# SAFMR_main.net
KiCad netlist of a schematic drawn in Altium Designer
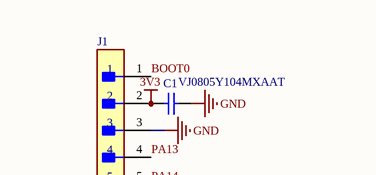
[diagram p0: SAFMR_main.SchDoc, top left]
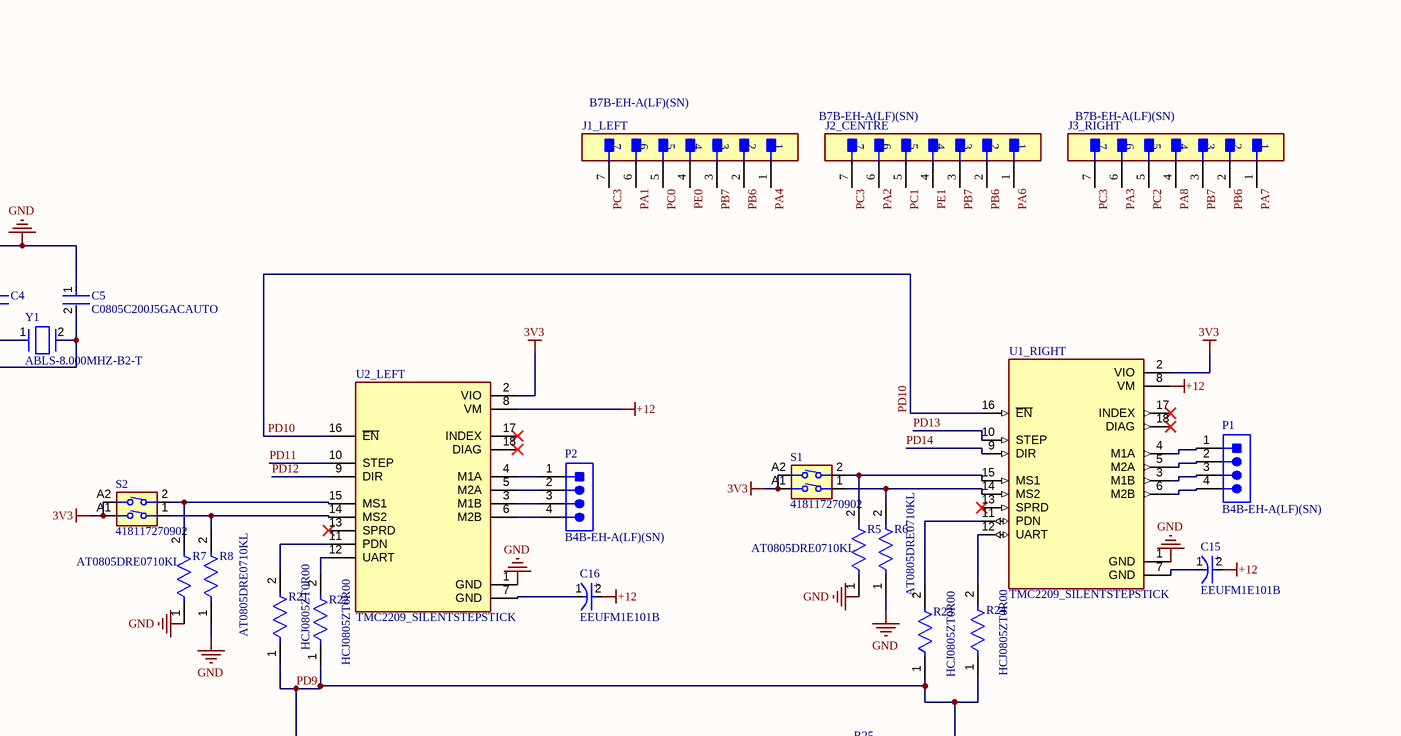
[diagram p1: SAFMR_main.SchDoc, top right]
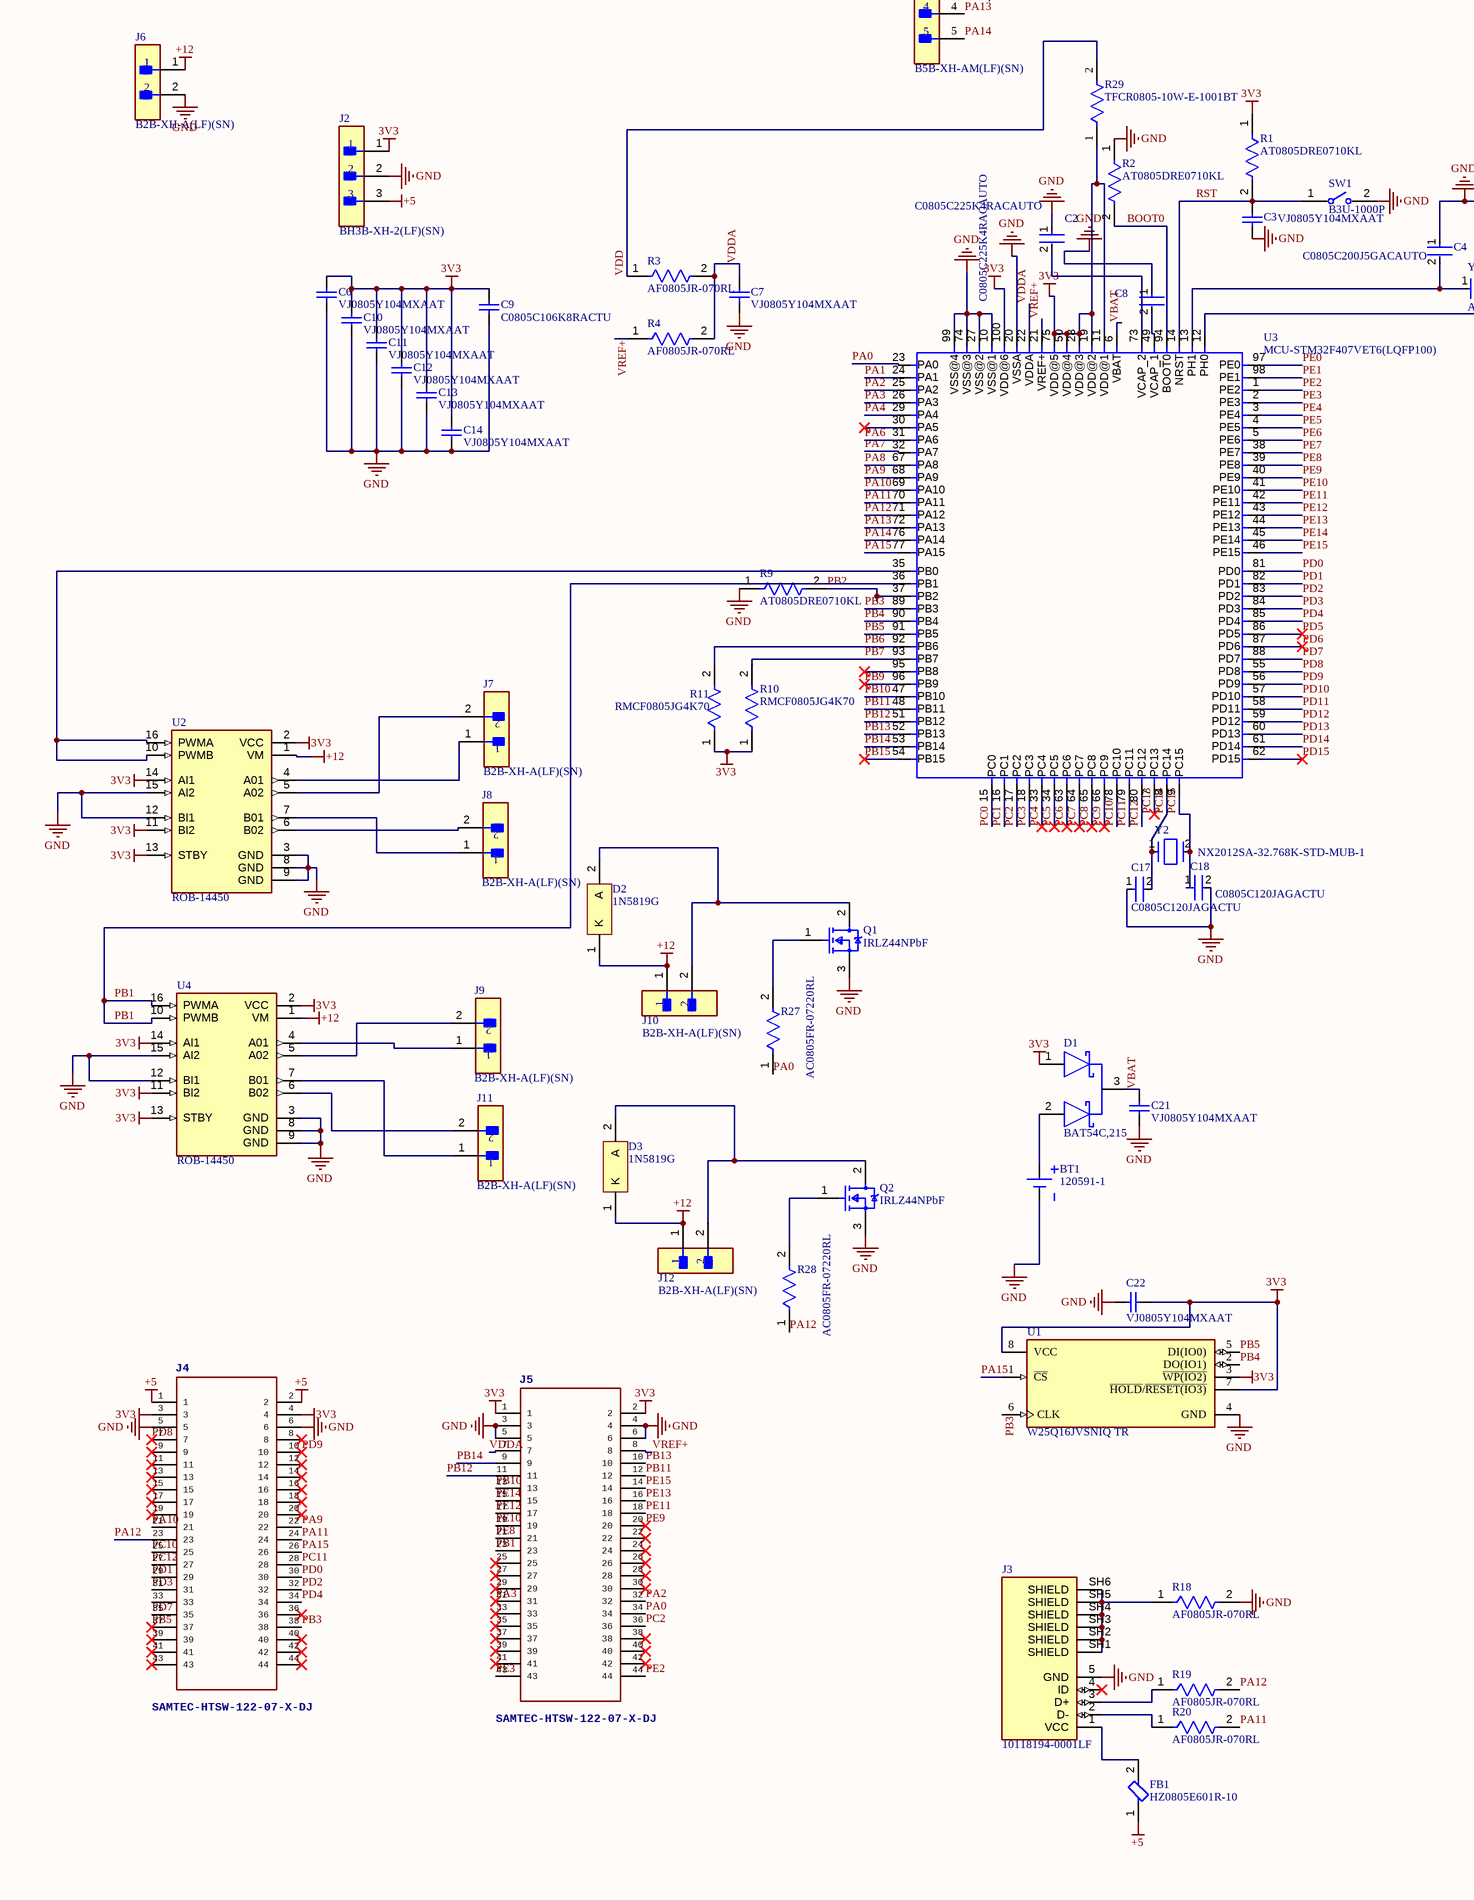
[diagram p2: SAFMR_main.SchDoc, bottom left]
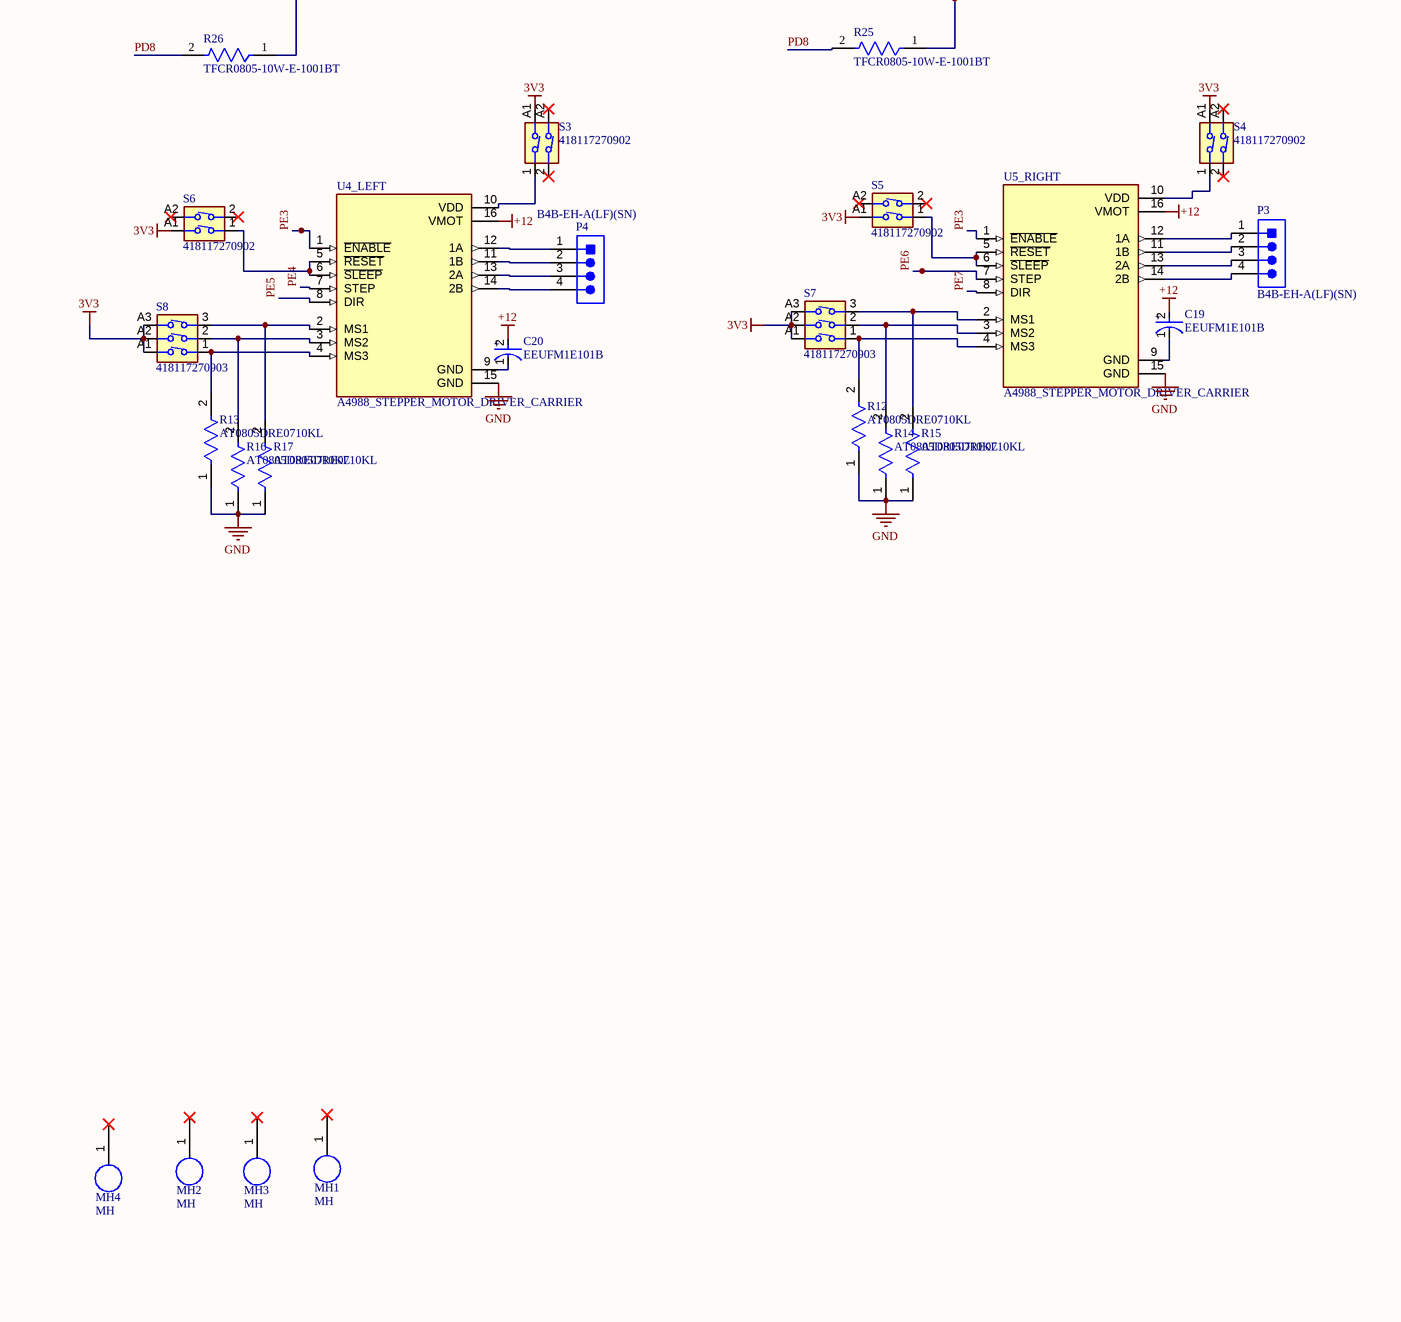
[diagram p3: SAFMR_main.SchDoc, bottom right]

(export (version "E")
  (design (tool "Eeschema 10.0.6"))
  (components
    (comp (ref "BT1")
      (value "120591-1")
      (footprint "TECO-120591-1-2_V")
      (description "Lithium Battery Holder for CR2032 3V Cell")
      (fields (field (name "MANUFACTURER") "TE Connectivity"))
      (libsource (lib "Altium Content Vault") (part "TECO-120591-1-2"))
    )
    (comp (ref "C1")
      (value "VJ0805Y104MXAAT")
      (footprint "CAPC2013X145X48NL20T23")
      (fields (field (name "MANUFACTURER") "Vitramon"))
      (libsource (lib "Altium Content Vault") (part "CAP"))
    )
    (comp (ref "C2")
      (value "C0805C225K4RACAUTO")
      (footprint "FP-C0805C225K4RACAUTO-MFG")
      (description "CAP CER 2.2UF 16V X7R 0805")
      (fields (field (name "TOLERANCE") "10%"))
      (libsource (lib "Altium Content Vault") (part "b4654b650e69147ec39a6b967a45e02"))
    )
    (comp (ref "C3")
      (value "VJ0805Y104MXAAT")
      (footprint "CAPC2013X145X48NL20T23")
      (fields (field (name "MANUFACTURER") "Vitramon"))
      (libsource (lib "Altium Content Vault") (part "CAP"))
    )
    (comp (ref "C4")
      (value "C0805C200J5GACAUTO")
      (footprint "FP-C0805C-DN-MFG")
      (description "C0805 20 pF C0G 30ppm/°C 5.00% 50 V")
      (fields (field (name "MANUFACTURER") "KEMET") (field (name "TOLERANCE") "0.05"))
      (libsource (lib "Altium Content Vault") (part "b4654b650e69147ec39a6b967a45e02"))
    )
    (comp (ref "C5")
      (value "C0805C200J5GACAUTO")
      (footprint "FP-C0805C-DN-MFG")
      (description "C0805 20 pF C0G 30ppm/°C 5.00% 50 V")
      (fields (field (name "MANUFACTURER") "KEMET") (field (name "TOLERANCE") "0.05"))
      (libsource (lib "Altium Content Vault") (part "b4654b650e69147ec39a6b967a45e02"))
    )
    (comp (ref "C6")
      (value "VJ0805Y104MXAAT")
      (footprint "CAPC2013X145X48NL20T23")
      (fields (field (name "MANUFACTURER") "Vitramon"))
      (libsource (lib "Altium Content Vault") (part "CAP"))
    )
    (comp (ref "C7")
      (value "VJ0805Y104MXAAT")
      (footprint "CAPC2013X145X48NL20T23")
      (fields (field (name "MANUFACTURER") "Vitramon"))
      (libsource (lib "Altium Content Vault") (part "CAP"))
    )
    (comp (ref "C8")
      (value "C0805C225K4RACAUTO")
      (footprint "FP-C0805C225K4RACAUTO-MFG")
      (description "CAP CER 2.2UF 16V X7R 0805")
      (fields (field (name "TOLERANCE") "10%"))
      (libsource (lib "Altium Content Vault") (part "b4654b650e69147ec39a6b967a45e02"))
    )
    (comp (ref "C9")
      (value "C0805C106K8RACTU")
      (footprint "CAPC2013X145X50LL20T25")
      (fields (field (name "MANUFACTURER") "Kemet"))
      (libsource (lib "Altium Content Vault") (part "CAP"))
    )
    (comp (ref "C10")
      (value "VJ0805Y104MXAAT")
      (footprint "CAPC2013X145X48NL20T23")
      (fields (field (name "MANUFACTURER") "Vitramon"))
      (libsource (lib "Altium Content Vault") (part "CAP"))
    )
    (comp (ref "C11")
      (value "VJ0805Y104MXAAT")
      (footprint "CAPC2013X145X48NL20T23")
      (fields (field (name "MANUFACTURER") "Vitramon"))
      (libsource (lib "Altium Content Vault") (part "CAP"))
    )
    (comp (ref "C12")
      (value "VJ0805Y104MXAAT")
      (footprint "CAPC2013X145X48NL20T23")
      (fields (field (name "MANUFACTURER") "Vitramon"))
      (libsource (lib "Altium Content Vault") (part "CAP"))
    )
    (comp (ref "C13")
      (value "VJ0805Y104MXAAT")
      (footprint "CAPC2013X145X48NL20T23")
      (fields (field (name "MANUFACTURER") "Vitramon"))
      (libsource (lib "Altium Content Vault") (part "CAP"))
    )
    (comp (ref "C14")
      (value "VJ0805Y104MXAAT")
      (footprint "CAPC2013X145X48NL20T23")
      (fields (field (name "MANUFACTURER") "Vitramon"))
      (libsource (lib "Altium Content Vault") (part "CAP"))
    )
    (comp (ref "C15")
      (value "EEUFM1E101B")
      (footprint "FP-RAD-TH-D_6_3_0_5-L_11-MFG")
      (description "Aluminum Electrolytic Capacitors (Radial Lead Type) 100uF ±20% 25V")
      (fields (field (name "TOLERANCE") "20%"))
      (libsource (lib "Altium Content Vault") (part "a00bbbee19879c290e62620ae7e47b1"))
    )
    (comp (ref "C16")
      (value "EEUFM1E101B")
      (footprint "FP-RAD-TH-D_6_3_0_5-L_11-MFG")
      (description "Aluminum Electrolytic Capacitors (Radial Lead Type) 100uF ±20% 25V")
      (fields (field (name "TOLERANCE") "20%"))
      (libsource (lib "Altium Content Vault") (part "a00bbbee19879c290e62620ae7e47b1"))
    )
    (comp (ref "C17")
      (value "C0805C120JAGACTU")
      (footprint "FP-C0805C-DN-MFG")
      (description "C0805 12 pF C0G 30ppm/°C 5.00% 250 V")
      (fields
        (field (name "MANUFACTURER") "KEMET")
        (field (name "OCTOPART") "https://octopart.com/c0805c120jagactu-kemet-88373179")
      )
      (libsource (lib "Altium Content Vault") (part "b4654b650e69147ec39a6b967a45e02"))
    )
    (comp (ref "C18")
      (value "C0805C120JAGACTU")
      (footprint "FP-C0805C-DN-MFG")
      (description "C0805 12 pF C0G 30ppm/°C 5.00% 250 V")
      (fields
        (field (name "MANUFACTURER") "KEMET")
        (field (name "OCTOPART") "https://octopart.com/c0805c120jagactu-kemet-88373179")
      )
      (libsource (lib "Altium Content Vault") (part "b4654b650e69147ec39a6b967a45e02"))
    )
    (comp (ref "C19")
      (value "EEUFM1E101B")
      (footprint "FP-RAD-TH-D_6_3_0_5-L_11-MFG")
      (description "Aluminum Electrolytic Capacitors (Radial Lead Type) 100uF ±20% 25V")
      (fields (field (name "TOLERANCE") "20%"))
      (libsource (lib "Altium Content Vault") (part "a00bbbee19879c290e62620ae7e47b1"))
    )
    (comp (ref "C20")
      (value "EEUFM1E101B")
      (footprint "FP-RAD-TH-D_6_3_0_5-L_11-MFG")
      (description "Aluminum Electrolytic Capacitors (Radial Lead Type) 100uF ±20% 25V")
      (fields (field (name "TOLERANCE") "20%"))
      (libsource (lib "Altium Content Vault") (part "a00bbbee19879c290e62620ae7e47b1"))
    )
    (comp (ref "C21")
      (value "VJ0805Y104MXAAT")
      (footprint "CAPC2013X145X48NL20T23")
      (fields (field (name "MANUFACTURER") "Vitramon"))
      (libsource (lib "Altium Content Vault") (part "CAP"))
    )
    (comp (ref "C22")
      (value "VJ0805Y104MXAAT")
      (footprint "CAPC2013X145X48NL20T23")
      (fields (field (name "MANUFACTURER") "Vitramon"))
      (libsource (lib "Altium Content Vault") (part "CAP"))
    )
    (comp (ref "D1")
      (value "BAT54C,215")
      (footprint "FP-SOT23-MFG")
      (description "DIODE ARRAY SCHOTTKY 30V SOT23")
      (fields
        (field (name "MANUFACTURER") "Nexperia")
        (field (name "OCTOPART") "https://octopart.com/bat54c%2C215-nexperia-78738945")
      )
      (libsource (lib "Altium Content Vault") (part "933c91619b22c421400e34e7415f7b4"))
    )
    (comp (ref "D2")
      (value "1N5819G")
      (footprint "ONSC-AXIAL_LEAD-2-59-10_P")
      (description "Rectifier, 2-Pin Axial_Lead, Pb-Free, Bulk Bag")
      (fields (field (name "MANUFACTURER") "On Semiconductor"))
      (libsource (lib "Altium Content Vault") (part "ONSC-D-K1A2-2_A"))
    )
    (comp (ref "D3")
      (value "1N5819G")
      (footprint "ONSC-AXIAL_LEAD-2-59-10_P")
      (description "Rectifier, 2-Pin Axial_Lead, Pb-Free, Bulk Bag")
      (fields (field (name "MANUFACTURER") "On Semiconductor"))
      (libsource (lib "Altium Content Vault") (part "ONSC-D-K1A2-2_A"))
    )
    (comp (ref "FB1")
      (value "HZ0805E601R-10")
      (footprint "FP-HZ0805-MFG")
      (description "FERRITE BEAD 600 OHM 0805 1LN")
      (libsource (lib "Altium Content Vault") (part "5f30dd21d616792df468990f7003faa"))
    )
    (comp (ref "J1")
      (value "B5B-XH-AM(LF)(SN)")
      (footprint "FP-B5B-XH-AM_LF_SN-MFG")
      (description "CONN HEADER VERT 5POS 2.5MM")
      (libsource (lib "Altium Content Vault") (part "bf93c07fd2649a848d0ec8585582aab"))
    )
    (comp (ref "J1_LEFT")
      (value "B7B-EH-A(LF)(SN)")
      (footprint "FP-B7B-EH-A_LF_SN-MFG")
      (description "CONN HEADER VERT 7POS 2.5MM")
      (libsource (lib "Altium Content Vault") (part "5bcee6b94e1fee4be3f4cc3a650a442"))
    )
    (comp (ref "J2")
      (value "BH3B-XH-2(LF)(SN)")
      (footprint "FP-BH3B-XH-2_LF_SN-MFG")
      (description "CONN HEADER VERT 3POS 2.5MM")
      (libsource (lib "Altium Content Vault") (part "0d3f023dd272f625e17a2be33dea85f"))
    )
    (comp (ref "J2_CENTRE")
      (value "B7B-EH-A(LF)(SN)")
      (footprint "FP-B7B-EH-A_LF_SN-MFG")
      (description "CONN HEADER VERT 7POS 2.5MM")
      (libsource (lib "Altium Content Vault") (part "5bcee6b94e1fee4be3f4cc3a650a442"))
    )
    (comp (ref "J3")
      (value "10118194-0001LF")
      (footprint "AMPHENOL_10118194-0001LF")
      (description "Micro USB, Input Output Connectors, B TYPE RECEPTACLE with flange")
      (fields (field (name "MF") "Amphenol ICC"))
      (libsource (lib "Schlib1") (part "10118194-0001LF"))
    )
    (comp (ref "J3_RIGHT")
      (value "B7B-EH-A(LF)(SN)")
      (footprint "FP-B7B-EH-A_LF_SN-MFG")
      (description "CONN HEADER VERT 7POS 2.5MM")
      (libsource (lib "Altium Content Vault") (part "5bcee6b94e1fee4be3f4cc3a650a442"))
    )
    (comp (ref "J4")
      (value "SAMTEC-HTSW-122-07-X-DJ")
      (footprint "SAMTEC-HTSW-122-07-X-D")
      (libsource (lib "SAMTEC-HTSW-122-07-X-D") (part "SAMTEC-HTSW-122-07-X-DJ"))
    )
    (comp (ref "J5")
      (value "SAMTEC-HTSW-122-07-X-DJ")
      (footprint "SAMTEC-HTSW-122-07-X-D")
      (libsource (lib "SAMTEC-HTSW-122-07-X-D") (part "SAMTEC-HTSW-122-07-X-DJ"))
    )
    (comp (ref "J6")
      (value "B2B-XH-A(LF)(SN)")
      (footprint "FP-B2B-XH-A_LF_SN-MFG")
      (description "CONN HEADER VERT 2POS 2.5MM")
      (libsource (lib "") (part "3bc925449376181038e59eaffc5286c_2"))
    )
    (comp (ref "J7")
      (value "B2B-XH-A(LF)(SN)")
      (footprint "FP-B2B-XH-A_LF_SN-MFG")
      (description "CONN HEADER VERT 2POS 2.5MM")
      (libsource (lib "Altium Content Vault") (part "3bc925449376181038e59eaffc5286c"))
    )
    (comp (ref "J8")
      (value "B2B-XH-A(LF)(SN)")
      (footprint "FP-B2B-XH-A_LF_SN-MFG")
      (description "CONN HEADER VERT 2POS 2.5MM")
      (libsource (lib "Altium Content Vault") (part "3bc925449376181038e59eaffc5286c"))
    )
    (comp (ref "J9")
      (value "B2B-XH-A(LF)(SN)")
      (footprint "FP-B2B-XH-A_LF_SN-MFG")
      (description "CONN HEADER VERT 2POS 2.5MM")
      (libsource (lib "Altium Content Vault") (part "3bc925449376181038e59eaffc5286c"))
    )
    (comp (ref "J10")
      (value "B2B-XH-A(LF)(SN)")
      (footprint "FP-B2B-XH-A_LF_SN-MFG")
      (description "CONN HEADER VERT 2POS 2.5MM")
      (libsource (lib "") (part "3bc925449376181038e59eaffc5286c_1"))
    )
    (comp (ref "J11")
      (value "B2B-XH-A(LF)(SN)")
      (footprint "FP-B2B-XH-A_LF_SN-MFG")
      (description "CONN HEADER VERT 2POS 2.5MM")
      (libsource (lib "Altium Content Vault") (part "3bc925449376181038e59eaffc5286c"))
    )
    (comp (ref "J12")
      (value "B2B-XH-A(LF)(SN)")
      (footprint "FP-B2B-XH-A_LF_SN-MFG")
      (description "CONN HEADER VERT 2POS 2.5MM")
      (libsource (lib "") (part "3bc925449376181038e59eaffc5286c_1"))
    )
    (comp (ref "MH1") (value "MH") (footprint "MH") (libsource (lib "Schlib1") (part "MH")))
    (comp (ref "MH2") (value "MH") (footprint "MH") (libsource (lib "Schlib1") (part "MH")))
    (comp (ref "MH3") (value "MH") (footprint "MH") (libsource (lib "Schlib1") (part "MH")))
    (comp (ref "MH4") (value "MH") (footprint "MH") (libsource (lib "Schlib1") (part "MH")))
    (comp (ref "P1")
      (value "B4B-EH-A(LF)(SN)")
      (footprint "JST-B4B-EH-A_V")
      (fields (field (name "MANUFACTURER") "JST"))
      (libsource (lib "Altium Content Vault") (part "CN-1P-M-R4"))
    )
    (comp (ref "P2")
      (value "B4B-EH-A(LF)(SN)")
      (footprint "JST-B4B-EH-A_V")
      (fields (field (name "MANUFACTURER") "JST"))
      (libsource (lib "Altium Content Vault") (part "CN-1P-M-R4"))
    )
    (comp (ref "P3")
      (value "B4B-EH-A(LF)(SN)")
      (footprint "JST-B4B-EH-A_V")
      (fields (field (name "MANUFACTURER") "JST"))
      (libsource (lib "Altium Content Vault") (part "CN-1P-M-R4"))
    )
    (comp (ref "P4")
      (value "B4B-EH-A(LF)(SN)")
      (footprint "JST-B4B-EH-A_V")
      (fields (field (name "MANUFACTURER") "JST"))
      (libsource (lib "Altium Content Vault") (part "CN-1P-M-R4"))
    )
    (comp (ref "Q1")
      (value "IRLZ44NPbF")
      (footprint "FP-PG-TO220-3-MFG")
      (description "MOSFET N-CH 55V 47A TO220AB")
      (libsource (lib "Altium Content Vault") (part "b09f7f152735e370c1ea22a33fa83d6"))
    )
    (comp (ref "Q2")
      (value "IRLZ44NPbF")
      (footprint "FP-PG-TO220-3-MFG")
      (description "MOSFET N-CH 55V 47A TO220AB")
      (libsource (lib "Altium Content Vault") (part "b09f7f152735e370c1ea22a33fa83d6"))
    )
    (comp (ref "R1")
      (value "AT0805DRE0710KL")
      (footprint "FP-AT0805-MFG")
      (description "Thin Film Chip Resistors Automotive Grade 10kΩ 0.5% 50ppm/°C 0805")
      (fields (field (name "TOLERANCE") "0.5%"))
      (libsource (lib "Altium Content Vault") (part "1029c3af85768c4190bb7ad29bc67b5"))
    )
    (comp (ref "R2")
      (value "AT0805DRE0710KL")
      (footprint "FP-AT0805-MFG")
      (description "Thin Film Chip Resistors Automotive Grade 10kΩ 0.5% 50ppm/°C 0805")
      (fields (field (name "TOLERANCE") "0.5%"))
      (libsource (lib "Altium Content Vault") (part "1029c3af85768c4190bb7ad29bc67b5"))
    )
    (comp (ref "R3")
      (value "AF0805JR-070RL")
      (footprint "FP-AF0805-IPC_B")
      (description "Anti-Sulfurated Chip Resistor Automotive Grade 0Ω Jumper 0.125W 0805")
      (libsource (lib "Altium Content Vault") (part "1029c3af85768c4190bb7ad29bc67b5"))
    )
    (comp (ref "R4")
      (value "AF0805JR-070RL")
      (footprint "FP-AF0805-IPC_B")
      (description "Anti-Sulfurated Chip Resistor Automotive Grade 0Ω Jumper 0.125W 0805")
      (libsource (lib "Altium Content Vault") (part "1029c3af85768c4190bb7ad29bc67b5"))
    )
    (comp (ref "R5")
      (value "AT0805DRE0710KL")
      (footprint "FP-AT0805-MFG")
      (description "Thin Film Chip Resistors Automotive Grade 10kΩ 0.5% 50ppm/°C 0805")
      (fields (field (name "TOLERANCE") "0.5%"))
      (libsource (lib "Altium Content Vault") (part "1029c3af85768c4190bb7ad29bc67b5"))
    )
    (comp (ref "R6")
      (value "AT0805DRE0710KL")
      (footprint "FP-AT0805-MFG")
      (description "Thin Film Chip Resistors Automotive Grade 10kΩ 0.5% 50ppm/°C 0805")
      (fields (field (name "TOLERANCE") "0.5%"))
      (libsource (lib "Altium Content Vault") (part "1029c3af85768c4190bb7ad29bc67b5"))
    )
    (comp (ref "R7")
      (value "AT0805DRE0710KL")
      (footprint "FP-AT0805-MFG")
      (description "Thin Film Chip Resistors Automotive Grade 10kΩ 0.5% 50ppm/°C 0805")
      (fields (field (name "TOLERANCE") "0.5%"))
      (libsource (lib "Altium Content Vault") (part "1029c3af85768c4190bb7ad29bc67b5"))
    )
    (comp (ref "R8")
      (value "AT0805DRE0710KL")
      (footprint "FP-AT0805-MFG")
      (description "Thin Film Chip Resistors Automotive Grade 10kΩ 0.5% 50ppm/°C 0805")
      (fields (field (name "TOLERANCE") "0.5%"))
      (libsource (lib "Altium Content Vault") (part "1029c3af85768c4190bb7ad29bc67b5"))
    )
    (comp (ref "R9")
      (value "AT0805DRE0710KL")
      (footprint "FP-AT0805-MFG")
      (description "Thin Film Chip Resistors Automotive Grade 10kΩ 0.5% 50ppm/°C 0805")
      (fields (field (name "TOLERANCE") "0.5%"))
      (libsource (lib "Altium Content Vault") (part "1029c3af85768c4190bb7ad29bc67b5"))
    )
    (comp (ref "R10")
      (value "RMCF0805JG4K70")
      (footprint "FP-RMCF0805-MFG")
      (description "4.7kΩ ±5% 0.125W 0805 Thick Film Chip Resistor AEC-Q200 compliant")
      (fields (field (name "TOLERANCE") "5%"))
      (libsource (lib "Altium Content Vault") (part "1029c3af85768c4190bb7ad29bc67b5"))
    )
    (comp (ref "R11")
      (value "RMCF0805JG4K70")
      (footprint "FP-RMCF0805-MFG")
      (description "4.7kΩ ±5% 0.125W 0805 Thick Film Chip Resistor AEC-Q200 compliant")
      (fields (field (name "TOLERANCE") "5%"))
      (libsource (lib "Altium Content Vault") (part "1029c3af85768c4190bb7ad29bc67b5"))
    )
    (comp (ref "R12")
      (value "AT0805DRE0710KL")
      (footprint "FP-AT0805-MFG")
      (description "Thin Film Chip Resistors Automotive Grade 10kΩ 0.5% 50ppm/°C 0805")
      (fields (field (name "TOLERANCE") "0.5%"))
      (libsource (lib "Altium Content Vault") (part "1029c3af85768c4190bb7ad29bc67b5"))
    )
    (comp (ref "R13")
      (value "AT0805DRE0710KL")
      (footprint "FP-AT0805-MFG")
      (description "Thin Film Chip Resistors Automotive Grade 10kΩ 0.5% 50ppm/°C 0805")
      (fields (field (name "TOLERANCE") "0.5%"))
      (libsource (lib "Altium Content Vault") (part "1029c3af85768c4190bb7ad29bc67b5"))
    )
    (comp (ref "R14")
      (value "AT0805DRE0710KL")
      (footprint "FP-AT0805-MFG")
      (description "Thin Film Chip Resistors Automotive Grade 10kΩ 0.5% 50ppm/°C 0805")
      (fields (field (name "TOLERANCE") "0.5%"))
      (libsource (lib "Altium Content Vault") (part "1029c3af85768c4190bb7ad29bc67b5"))
    )
    (comp (ref "R15")
      (value "AT0805DRE0710KL")
      (footprint "FP-AT0805-MFG")
      (description "Thin Film Chip Resistors Automotive Grade 10kΩ 0.5% 50ppm/°C 0805")
      (fields (field (name "TOLERANCE") "0.5%"))
      (libsource (lib "Altium Content Vault") (part "1029c3af85768c4190bb7ad29bc67b5"))
    )
    (comp (ref "R16")
      (value "AT0805DRE0710KL")
      (footprint "FP-AT0805-MFG")
      (description "Thin Film Chip Resistors Automotive Grade 10kΩ 0.5% 50ppm/°C 0805")
      (fields (field (name "TOLERANCE") "0.5%"))
      (libsource (lib "Altium Content Vault") (part "1029c3af85768c4190bb7ad29bc67b5"))
    )
    (comp (ref "R17")
      (value "AT0805DRE0710KL")
      (footprint "FP-AT0805-MFG")
      (description "Thin Film Chip Resistors Automotive Grade 10kΩ 0.5% 50ppm/°C 0805")
      (fields (field (name "TOLERANCE") "0.5%"))
      (libsource (lib "Altium Content Vault") (part "1029c3af85768c4190bb7ad29bc67b5"))
    )
    (comp (ref "R18")
      (value "AF0805JR-070RL")
      (footprint "FP-AF0805-IPC_B")
      (description "Anti-Sulfurated Chip Resistor Automotive Grade 0Ω Jumper 0.125W 0805")
      (libsource (lib "Altium Content Vault") (part "1029c3af85768c4190bb7ad29bc67b5"))
    )
    (comp (ref "R19")
      (value "AF0805JR-070RL")
      (footprint "FP-AF0805-IPC_B")
      (description "Anti-Sulfurated Chip Resistor Automotive Grade 0Ω Jumper 0.125W 0805")
      (libsource (lib "Altium Content Vault") (part "1029c3af85768c4190bb7ad29bc67b5"))
    )
    (comp (ref "R20")
      (value "AF0805JR-070RL")
      (footprint "FP-AF0805-IPC_B")
      (description "Anti-Sulfurated Chip Resistor Automotive Grade 0Ω Jumper 0.125W 0805")
      (libsource (lib "Altium Content Vault") (part "1029c3af85768c4190bb7ad29bc67b5"))
    )
    (comp (ref "R21")
      (value "HCJ0805ZT0R00")
      (footprint "FP-HCJ0805-MFG")
      (description "RES 0 OHM JUMPER 1/2W 0805")
      (libsource (lib "Altium Content Vault") (part "1029c3af85768c4190bb7ad29bc67b5"))
    )
    (comp (ref "R22")
      (value "HCJ0805ZT0R00")
      (footprint "FP-HCJ0805-MFG")
      (description "RES 0 OHM JUMPER 1/2W 0805")
      (libsource (lib "Altium Content Vault") (part "1029c3af85768c4190bb7ad29bc67b5"))
    )
    (comp (ref "R23")
      (value "HCJ0805ZT0R00")
      (footprint "FP-HCJ0805-MFG")
      (description "RES 0 OHM JUMPER 1/2W 0805")
      (libsource (lib "Altium Content Vault") (part "1029c3af85768c4190bb7ad29bc67b5"))
    )
    (comp (ref "R24")
      (value "HCJ0805ZT0R00")
      (footprint "FP-HCJ0805-MFG")
      (description "RES 0 OHM JUMPER 1/2W 0805")
      (libsource (lib "Altium Content Vault") (part "1029c3af85768c4190bb7ad29bc67b5"))
    )
    (comp (ref "R25")
      (value "TFCR0805-10W-E-1001BT")
      (footprint "FP-TFCR0805-IPC_A")
      (description "RES Thin Film,  1kΩ, 0.1%, 0.1W, 25ppm/°C, 0805")
      (libsource (lib "Altium Content Vault") (part "1029c3af85768c4190bb7ad29bc67b5"))
    )
    (comp (ref "R26")
      (value "TFCR0805-10W-E-1001BT")
      (footprint "FP-TFCR0805-IPC_A")
      (description "RES Thin Film,  1kΩ, 0.1%, 0.1W, 25ppm/°C, 0805")
      (libsource (lib "Altium Content Vault") (part "1029c3af85768c4190bb7ad29bc67b5"))
    )
    (comp (ref "R27")
      (value "AC0805FR-07220RL")
      (footprint "FP-AC0805-MFG")
      (description "RES SMD 220 OHM 1% 1/8W 0805")
      (fields
        (field (name "OCTOPART") "https://octopart.com/ac0805fr-07220rl-yageo-26041145")
        (field (name "TOLERANCE") "0.01")
      )
      (libsource (lib "Altium Content Vault") (part "1029c3af85768c4190bb7ad29bc67b5"))
    )
    (comp (ref "R28")
      (value "AC0805FR-07220RL")
      (footprint "FP-AC0805-MFG")
      (description "RES SMD 220 OHM 1% 1/8W 0805")
      (fields
        (field (name "OCTOPART") "https://octopart.com/ac0805fr-07220rl-yageo-26041145")
        (field (name "TOLERANCE") "0.01")
      )
      (libsource (lib "Altium Content Vault") (part "1029c3af85768c4190bb7ad29bc67b5"))
    )
    (comp (ref "R29")
      (value "TFCR0805-10W-E-1001BT")
      (footprint "FP-TFCR0805-IPC_A")
      (description "RES Thin Film,  1kΩ, 0.1%, 0.1W, 25ppm/°C, 0805")
      (libsource (lib "Altium Content Vault") (part "1029c3af85768c4190bb7ad29bc67b5"))
    )
    (comp (ref "S1")
      (value "418117270902")
      (footprint "418117270902")
      (description "Dip Switch SPST 2 Position Through Hole Slide (Standard) Actuator 25mA 24VDC")
      (fields (field (name "MF") "WÃ¼rth Elektronik"))
      (libsource (lib "") (part "418117270902_1"))
    )
    (comp (ref "S2")
      (value "418117270902")
      (footprint "418117270902")
      (description "Dip Switch SPST 2 Position Through Hole Slide (Standard) Actuator 25mA 24VDC")
      (fields (field (name "MF") "WÃ¼rth Elektronik"))
      (libsource (lib "") (part "418117270902_1"))
    )
    (comp (ref "S3")
      (value "418117270902")
      (footprint "418117270902")
      (description "Dip Switch SPST 2 Position Through Hole Slide (Standard) Actuator 25mA 24VDC")
      (fields (field (name "MF") "WÃ¼rth Elektronik"))
      (libsource (lib "Schlib1") (part "418117270902"))
    )
    (comp (ref "S4")
      (value "418117270902")
      (footprint "418117270902")
      (description "Dip Switch SPST 2 Position Through Hole Slide (Standard) Actuator 25mA 24VDC")
      (fields (field (name "MF") "WÃ¼rth Elektronik"))
      (libsource (lib "Schlib1") (part "418117270902"))
    )
    (comp (ref "S5")
      (value "418117270902")
      (footprint "418117270902")
      (description "Dip Switch SPST 2 Position Through Hole Slide (Standard) Actuator 25mA 24VDC")
      (fields (field (name "MF") "WÃ¼rth Elektronik"))
      (libsource (lib "") (part "418117270902_1"))
    )
    (comp (ref "S6")
      (value "418117270902")
      (footprint "418117270902")
      (description "Dip Switch SPST 2 Position Through Hole Slide (Standard) Actuator 25mA 24VDC")
      (fields (field (name "MF") "WÃ¼rth Elektronik"))
      (libsource (lib "") (part "418117270902_1"))
    )
    (comp (ref "S7")
      (value "418117270903")
      (footprint "418117270903")
      (description "Dip Switch SPST 3 Position Through Hole Slide (Standard) Actuator 25mA 24VDC")
      (fields (field (name "MF") "WÃ¼rth Elektronik"))
      (libsource (lib "Schlib1") (part "418117270903"))
    )
    (comp (ref "S8")
      (value "418117270903")
      (footprint "418117270903")
      (description "Dip Switch SPST 3 Position Through Hole Slide (Standard) Actuator 25mA 24VDC")
      (fields (field (name "MF") "WÃ¼rth Elektronik"))
      (libsource (lib "Schlib1") (part "418117270903"))
    )
    (comp (ref "SW1")
      (value "B3U-1000P")
      (footprint "FP-B3U-1000P-MFG")
      (description "SWITCH TACTILE SPST-NO 0.05A 12V")
      (libsource (lib "Altium Content Vault") (part "ae622034201233ca1abcedc05908f33"))
    )
    (comp (ref "U1")
      (value "W25Q16JVSNIQ TR")
      (footprint "FP-W25Q16JVSNIQ_TR-IPC_A")
      (description "IC FLASH 16MBIT SPI/QUAD 8SOIC")
      (libsource (lib "Altium Content Vault") (part "bca9062cdd4fd3591131373229c4e34"))
    )
    (comp (ref "U1_RIGHT")
      (value "TMC2209_SILENTSTEPSTICK")
      (footprint "MODULE_TMC2209_SILENTSTEPSTICK")
      (description "TMC2209 Motor Controller/Driver Power Management Evaluation Board")
      (fields
        (field (name "MF") "Trinamic Motion Control GmbH")
        (field (name "MP") "TMC2209 SILENTSTEPSTICK")
      )
      (libsource (lib "TMC2209_SILENTSTEPSTICK") (part "TMC2209_SILENTSTEPSTICK"))
    )
    (comp (ref "U2")
      (value "ROB-14450")
      (footprint "PcbLib2:MODULE_ROB-14450")
      (description "TB6612FNG Motor Controller/Driver Power Management Evaluation Board")
      (fields (field (name "MF") "SparkFun Electronics"))
      (libsource (lib "Schlib1") (part "ROB-14450"))
    )
    (comp (ref "U2_LEFT")
      (value "TMC2209_SILENTSTEPSTICK")
      (footprint "MODULE_TMC2209_SILENTSTEPSTICK")
      (description "TMC2209 Motor Controller/Driver Power Management Evaluation Board")
      (fields
        (field (name "MF") "Trinamic Motion Control GmbH")
        (field (name "MP") "TMC2209 SILENTSTEPSTICK")
      )
      (libsource (lib "TMC2209_SILENTSTEPSTICK") (part "TMC2209_SILENTSTEPSTICK"))
    )
    (comp (ref "U3")
      (value "MCU-STM32F407VET6(LQFP100)")
      (footprint "LQFP100-0.5-13.8X13.8MM")
      (fields (field (name "MP") "STM32F407VET6") (field (name "MF") "STMicroelectronics"))
      (libsource (lib "MCU-STM32F407VET6_LQFP100_") (part "MCU-STM32F407VET6(LQFP100)"))
    )
    (comp (ref "U4")
      (value "ROB-14450")
      (footprint "PcbLib2:MODULE_ROB-14450")
      (description "TB6612FNG Motor Controller/Driver Power Management Evaluation Board")
      (fields (field (name "MF") "SparkFun Electronics"))
      (libsource (lib "Schlib1") (part "ROB-14450"))
    )
    (comp (ref "U4_LEFT")
      (value "A4988_STEPPER_MOTOR_DRIVER_CARRIER")
      (footprint "MODULE_A4988_STEPPER_MOTOR_DRIVER_CARRIER")
      (description "Stepper motor controler; IC: A4988; 1A; Uin mot: 8Ã·35V")
      (libsource (lib "A4988_STEPPER_MOTOR_DRIVER_CARRIER") (part "A4988_STEPPER_MOTOR_DRIVER_CARRIER"))
    )
    (comp (ref "U5_RIGHT")
      (value "A4988_STEPPER_MOTOR_DRIVER_CARRIER")
      (footprint "MODULE_A4988_STEPPER_MOTOR_DRIVER_CARRIER")
      (description "Stepper motor controler; IC: A4988; 1A; Uin mot: 8Ã·35V")
      (libsource (lib "A4988_STEPPER_MOTOR_DRIVER_CARRIER") (part "A4988_STEPPER_MOTOR_DRIVER_CARRIER"))
    )
    (comp (ref "Y1")
      (value "ABLS-8.000MHZ-B2-T")
      (footprint "FP-ABLS-MFG")
      (description "CRYSTAL 8.0000MHZ 18PF SMD")
      (fields (field (name "TOLERANCE") "20ppm"))
      (libsource (lib "Altium Content Vault") (part "c23a69dc6c9e2f18f2079038eb95dd1"))
    )
    (comp (ref "Y2")
      (value "NX2012SA-32.768K-STD-MUB-1")
      (footprint "FP-NX2012SA-MFG")
      (description "CRYSTAL 32.7680KHZ 12.5PF SMD")
      (libsource (lib "Altium Content Vault") (part "c23a69dc6c9e2f18f2079038eb95dd1"))
    )
  )
  (nets
    (net (code "1") (name "+5") (class "Default")
      (node (ref "FB1") (pin "1") (pinfunction "1_1") (pintype "passive"))
      (node (ref "J2") (pin "3") (pinfunction "3_3") (pintype "passive"))
      (node (ref "J4") (pin "1") (pinfunction "1_1") (pintype "passive"))
      (node (ref "J4") (pin "2") (pinfunction "2_2") (pintype "passive"))
    )
    (net (code "2") (name "+12") (class "Default")
      (node (ref "C15") (pin "2") (pinfunction "A_2") (pintype "passive"))
      (node (ref "C16") (pin "2") (pinfunction "A_2") (pintype "passive"))
      (node (ref "C19") (pin "2") (pinfunction "A_2") (pintype "passive"))
      (node (ref "C20") (pin "2") (pinfunction "A_2") (pintype "passive"))
      (node (ref "D2") (pin "1") (pinfunction "K_1") (pintype "passive"))
      (node (ref "D3") (pin "1") (pinfunction "K_1") (pintype "passive"))
      (node (ref "J10") (pin "1") (pinfunction "1_1") (pintype "passive"))
      (node (ref "J12") (pin "1") (pinfunction "1_1") (pintype "passive"))
      (node (ref "J6") (pin "1") (pinfunction "1_1") (pintype "passive"))
      (node (ref "U1_RIGHT") (pin "8") (pinfunction "VM_8") (pintype "passive"))
      (node (ref "U2") (pin "1") (pinfunction "VM_1") (pintype "power_in"))
      (node (ref "U2_LEFT") (pin "8") (pinfunction "VM_8") (pintype "passive"))
      (node (ref "U4") (pin "1") (pinfunction "VM_1") (pintype "power_in"))
      (node (ref "U4_LEFT") (pin "16") (pinfunction "VMOT_16") (pintype "power_in"))
      (node (ref "U5_RIGHT") (pin "16") (pinfunction "VMOT_16") (pintype "power_in"))
    )
    (net (code "3") (name "/BOOT0") (class "Default")
      (node (ref "J1") (pin "1") (pinfunction "1_1") (pintype "passive"))
      (node (ref "R2") (pin "2") (pinfunction "2_2") (pintype "passive"))
      (node (ref "U3") (pin "94") (pinfunction "BOOT0_94") (pintype "bidirectional"))
    )
    (net (code "4") (name "/PA0") (class "Default")
      (node (ref "J5") (pin "34") (pinfunction "34_34") (pintype "passive"))
      (node (ref "R27") (pin "1") (pinfunction "1_1") (pintype "passive"))
      (node (ref "U3") (pin "23") (pinfunction "PA0_23") (pintype "bidirectional"))
    )
    (net (code "5") (name "/PA1") (class "Default")
      (node (ref "J1_LEFT") (pin "6") (pinfunction "6_6") (pintype "passive"))
      (node (ref "U3") (pin "24") (pinfunction "PA1_24") (pintype "bidirectional"))
    )
    (net (code "6") (name "/PA2") (class "Default")
      (node (ref "J2_CENTRE") (pin "6") (pinfunction "6_6") (pintype "passive"))
      (node (ref "J5") (pin "32") (pinfunction "32_32") (pintype "passive"))
      (node (ref "U3") (pin "25") (pinfunction "PA2_25") (pintype "bidirectional"))
    )
    (net (code "7") (name "/PA3") (class "Default")
      (node (ref "J3_RIGHT") (pin "6") (pinfunction "6_6") (pintype "passive"))
      (node (ref "J5") (pin "31") (pinfunction "31_31") (pintype "passive"))
      (node (ref "U3") (pin "26") (pinfunction "PA3_26") (pintype "bidirectional"))
    )
    (net (code "8") (name "/PA4") (class "Default")
      (node (ref "J1_LEFT") (pin "1") (pinfunction "1_1") (pintype "passive"))
      (node (ref "U3") (pin "29") (pinfunction "PA4_29") (pintype "bidirectional"))
    )
    (net (code "9") (name "/PA6") (class "Default")
      (node (ref "J2_CENTRE") (pin "1") (pinfunction "1_1") (pintype "passive"))
      (node (ref "U3") (pin "31") (pinfunction "PA6_31") (pintype "bidirectional"))
    )
    (net (code "10") (name "/PA7") (class "Default")
      (node (ref "J3_RIGHT") (pin "1") (pinfunction "1_1") (pintype "passive"))
      (node (ref "U3") (pin "32") (pinfunction "PA7_32") (pintype "bidirectional"))
    )
    (net (code "11") (name "/PA8") (class "Default")
      (node (ref "J3_RIGHT") (pin "4") (pinfunction "4_4") (pintype "passive"))
      (node (ref "U3") (pin "67") (pinfunction "PA8_67") (pintype "bidirectional"))
    )
    (net (code "12") (name "/PA9") (class "Default")
      (node (ref "J4") (pin "22") (pinfunction "22_22") (pintype "passive"))
      (node (ref "U3") (pin "68") (pinfunction "PA9_68") (pintype "bidirectional"))
    )
    (net (code "13") (name "/PA10") (class "Default")
      (node (ref "J4") (pin "21") (pinfunction "21_21") (pintype "passive"))
      (node (ref "U3") (pin "69") (pinfunction "PA10_69") (pintype "bidirectional"))
    )
    (net (code "14") (name "/PA11") (class "Default")
      (node (ref "J4") (pin "24") (pinfunction "24_24") (pintype "passive"))
      (node (ref "R20") (pin "2") (pinfunction "2_2") (pintype "passive"))
      (node (ref "U3") (pin "70") (pinfunction "PA11_70") (pintype "bidirectional"))
    )
    (net (code "15") (name "/PA12") (class "Default")
      (node (ref "J4") (pin "23") (pinfunction "23_23") (pintype "passive"))
      (node (ref "R19") (pin "2") (pinfunction "2_2") (pintype "passive"))
      (node (ref "R28") (pin "1") (pinfunction "1_1") (pintype "passive"))
      (node (ref "U3") (pin "71") (pinfunction "PA12_71") (pintype "bidirectional"))
    )
    (net (code "16") (name "/PA13") (class "Default")
      (node (ref "J1") (pin "4") (pinfunction "4_4") (pintype "passive"))
      (node (ref "U3") (pin "72") (pinfunction "PA13_72") (pintype "bidirectional"))
    )
    (net (code "17") (name "/PA14") (class "Default")
      (node (ref "J1") (pin "5") (pinfunction "5_5") (pintype "passive"))
      (node (ref "U3") (pin "76") (pinfunction "PA14_76") (pintype "bidirectional"))
    )
    (net (code "18") (name "/PA15") (class "Default")
      (node (ref "J4") (pin "26") (pinfunction "26_26") (pintype "passive"))
      (node (ref "U1") (pin "1") (pinfunction "~{CS}_1") (pintype "input"))
      (node (ref "U3") (pin "77") (pinfunction "PA15_77") (pintype "bidirectional"))
    )
    (net (code "19") (name "/PB1") (class "Default")
      (node (ref "J5") (pin "23") (pinfunction "23_23") (pintype "passive"))
      (node (ref "U3") (pin "36") (pinfunction "PB1_36") (pintype "passive"))
      (node (ref "U4") (pin "10") (pinfunction "PWMB_10") (pintype "input"))
      (node (ref "U4") (pin "16") (pinfunction "PWMA_16") (pintype "input"))
    )
    (net (code "20") (name "/PB2") (class "Default")
      (node (ref "R9") (pin "2") (pinfunction "2_2") (pintype "passive"))
      (node (ref "U3") (pin "37") (pinfunction "PB2_37") (pintype "bidirectional"))
    )
    (net (code "21") (name "/PB3") (class "Default")
      (node (ref "J4") (pin "38") (pinfunction "38_38") (pintype "passive"))
      (node (ref "U1") (pin "6") (pinfunction "CLK_6") (pintype "input"))
      (node (ref "U3") (pin "89") (pinfunction "PB3_89") (pintype "bidirectional"))
    )
    (net (code "22") (name "/PB4") (class "Default")
      (node (ref "U1") (pin "2") (pinfunction "DO(IO1)_2") (pintype "bidirectional"))
      (node (ref "U3") (pin "90") (pinfunction "PB4_90") (pintype "bidirectional"))
    )
    (net (code "23") (name "/PB5") (class "Default")
      (node (ref "J4") (pin "37") (pinfunction "37_37") (pintype "passive"))
      (node (ref "U1") (pin "5") (pinfunction "DI(IO0)_5") (pintype "bidirectional"))
      (node (ref "U3") (pin "91") (pinfunction "PB5_91") (pintype "bidirectional"))
    )
    (net (code "24") (name "/PB6") (class "Default")
      (node (ref "J1_LEFT") (pin "2") (pinfunction "2_2") (pintype "passive"))
      (node (ref "J2_CENTRE") (pin "2") (pinfunction "2_2") (pintype "passive"))
      (node (ref "J3_RIGHT") (pin "2") (pinfunction "2_2") (pintype "passive"))
      (node (ref "R11") (pin "2") (pinfunction "2_2") (pintype "passive"))
      (node (ref "U3") (pin "92") (pinfunction "PB6_92") (pintype "bidirectional"))
    )
    (net (code "25") (name "/PB7") (class "Default")
      (node (ref "J1_LEFT") (pin "3") (pinfunction "3_3") (pintype "passive"))
      (node (ref "J2_CENTRE") (pin "3") (pinfunction "3_3") (pintype "passive"))
      (node (ref "J3_RIGHT") (pin "3") (pinfunction "3_3") (pintype "passive"))
      (node (ref "R10") (pin "2") (pinfunction "2_2") (pintype "passive"))
      (node (ref "U3") (pin "93") (pinfunction "PB7_93") (pintype "bidirectional"))
    )
    (net (code "26") (name "/PB9") (class "Default")
      (node (ref "U3") (pin "96") (pinfunction "PB9_96") (pintype "bidirectional+no_connect"))
    )
    (net (code "27") (name "/PB10") (class "Default")
      (node (ref "J5") (pin "13") (pinfunction "13_13") (pintype "passive"))
      (node (ref "U3") (pin "47") (pinfunction "PB10_47") (pintype "bidirectional"))
    )
    (net (code "28") (name "/PB11") (class "Default")
      (node (ref "J5") (pin "12") (pinfunction "12_12") (pintype "passive"))
      (node (ref "U3") (pin "48") (pinfunction "PB11_48") (pintype "bidirectional"))
    )
    (net (code "29") (name "/PB12") (class "Default")
      (node (ref "J5") (pin "11") (pinfunction "11_11") (pintype "passive"))
      (node (ref "U3") (pin "51") (pinfunction "PB12_51") (pintype "bidirectional"))
    )
    (net (code "30") (name "/PB13") (class "Default")
      (node (ref "J5") (pin "10") (pinfunction "10_10") (pintype "passive"))
      (node (ref "U3") (pin "52") (pinfunction "PB13_52") (pintype "bidirectional"))
    )
    (net (code "31") (name "/PB14") (class "Default")
      (node (ref "J5") (pin "9") (pinfunction "9_9") (pintype "passive"))
      (node (ref "U3") (pin "53") (pinfunction "PB14_53") (pintype "bidirectional"))
    )
    (net (code "32") (name "/PB15") (class "Default")
      (node (ref "U3") (pin "54") (pinfunction "PB15_54") (pintype "bidirectional+no_connect"))
    )
    (net (code "33") (name "/PC0") (class "Default")
      (node (ref "J1_LEFT") (pin "5") (pinfunction "5_5") (pintype "passive"))
      (node (ref "U3") (pin "15") (pinfunction "PC0_15") (pintype "bidirectional"))
    )
    (net (code "34") (name "/PC1") (class "Default")
      (node (ref "J2_CENTRE") (pin "5") (pinfunction "5_5") (pintype "passive"))
      (node (ref "U3") (pin "16") (pinfunction "PC1_16") (pintype "bidirectional"))
    )
    (net (code "35") (name "/PC2") (class "Default")
      (node (ref "J3_RIGHT") (pin "5") (pinfunction "5_5") (pintype "passive"))
      (node (ref "J5") (pin "36") (pinfunction "36_36") (pintype "passive"))
      (node (ref "U3") (pin "17") (pinfunction "PC2_17") (pintype "bidirectional"))
    )
    (net (code "36") (name "/PC3") (class "Default")
      (node (ref "J1_LEFT") (pin "7") (pinfunction "7_7") (pintype "passive"))
      (node (ref "J2_CENTRE") (pin "7") (pinfunction "7_7") (pintype "passive"))
      (node (ref "J3_RIGHT") (pin "7") (pinfunction "7_7") (pintype "passive"))
      (node (ref "U3") (pin "18") (pinfunction "PC3_18") (pintype "bidirectional"))
    )
    (net (code "37") (name "/PC4") (class "Default")
      (node (ref "U3") (pin "33") (pinfunction "PC4_33") (pintype "bidirectional+no_connect"))
    )
    (net (code "38") (name "/PC5") (class "Default")
      (node (ref "U3") (pin "34") (pinfunction "PC5_34") (pintype "bidirectional+no_connect"))
    )
    (net (code "39") (name "/PC6") (class "Default")
      (node (ref "U3") (pin "63") (pinfunction "PC6_63") (pintype "bidirectional+no_connect"))
    )
    (net (code "40") (name "/PC7") (class "Default")
      (node (ref "U3") (pin "64") (pinfunction "PC7_64") (pintype "bidirectional+no_connect"))
    )
    (net (code "41") (name "/PC8") (class "Default")
      (node (ref "U3") (pin "65") (pinfunction "PC8_65") (pintype "bidirectional+no_connect"))
    )
    (net (code "42") (name "/PC9") (class "Default")
      (node (ref "U3") (pin "66") (pinfunction "PC9_66") (pintype "bidirectional+no_connect"))
    )
    (net (code "43") (name "/PC10") (class "Default")
      (node (ref "J4") (pin "25") (pinfunction "25_25") (pintype "passive"))
      (node (ref "U3") (pin "78") (pinfunction "PC10_78") (pintype "bidirectional"))
    )
    (net (code "44") (name "/PC11") (class "Default")
      (node (ref "J4") (pin "28") (pinfunction "28_28") (pintype "passive"))
      (node (ref "U3") (pin "79") (pinfunction "PC11_79") (pintype "bidirectional"))
    )
    (net (code "45") (name "/PC12") (class "Default")
      (node (ref "J4") (pin "27") (pinfunction "27_27") (pintype "passive"))
      (node (ref "U3") (pin "80") (pinfunction "PC12_80") (pintype "bidirectional"))
    )
    (net (code "46") (name "/PC13") (class "Default")
      (node (ref "U3") (pin "7") (pinfunction "PC13_7") (pintype "bidirectional+no_connect"))
    )
    (net (code "47") (name "/PC14") (class "Default")
      (node (ref "C17") (pin "2") (pinfunction "2_2") (pintype "passive"))
      (node (ref "U3") (pin "8") (pinfunction "PC14_8") (pintype "bidirectional"))
      (node (ref "Y2") (pin "1") (pinfunction "1_1") (pintype "passive"))
    )
    (net (code "48") (name "/PC15") (class "Default")
      (node (ref "C18") (pin "1") (pinfunction "1_1") (pintype "passive"))
      (node (ref "U3") (pin "9") (pinfunction "PC15_9") (pintype "bidirectional"))
      (node (ref "Y2") (pin "2") (pinfunction "2_2") (pintype "passive"))
    )
    (net (code "49") (name "/PD0") (class "Default")
      (node (ref "J4") (pin "30") (pinfunction "30_30") (pintype "passive"))
      (node (ref "U3") (pin "81") (pinfunction "PD0_81") (pintype "bidirectional"))
    )
    (net (code "50") (name "/PD1") (class "Default")
      (node (ref "J4") (pin "29") (pinfunction "29_29") (pintype "passive"))
      (node (ref "U3") (pin "82") (pinfunction "PD1_82") (pintype "bidirectional"))
    )
    (net (code "51") (name "/PD2") (class "Default")
      (node (ref "J4") (pin "32") (pinfunction "32_32") (pintype "passive"))
      (node (ref "U3") (pin "83") (pinfunction "PD2_83") (pintype "bidirectional"))
    )
    (net (code "52") (name "/PD3") (class "Default")
      (node (ref "J4") (pin "31") (pinfunction "31_31") (pintype "passive"))
      (node (ref "U3") (pin "84") (pinfunction "PD3_84") (pintype "bidirectional"))
    )
    (net (code "53") (name "/PD4") (class "Default")
      (node (ref "J4") (pin "34") (pinfunction "34_34") (pintype "passive"))
      (node (ref "U3") (pin "85") (pinfunction "PD4_85") (pintype "bidirectional"))
    )
    (net (code "54") (name "/PD5") (class "Default")
      (node (ref "U3") (pin "86") (pinfunction "PD5_86") (pintype "bidirectional+no_connect"))
    )
    (net (code "55") (name "/PD6") (class "Default")
      (node (ref "U3") (pin "87") (pinfunction "PD6_87") (pintype "bidirectional+no_connect"))
    )
    (net (code "56") (name "/PD7") (class "Default")
      (node (ref "J4") (pin "35") (pinfunction "35_35") (pintype "passive"))
      (node (ref "U3") (pin "88") (pinfunction "PD7_88") (pintype "bidirectional"))
    )
    (net (code "57") (name "/PD8") (class "Default")
      (node (ref "J4") (pin "7") (pinfunction "7_7") (pintype "passive"))
      (node (ref "R25") (pin "2") (pinfunction "2_2") (pintype "passive"))
      (node (ref "R26") (pin "2") (pinfunction "2_2") (pintype "passive"))
      (node (ref "U3") (pin "55") (pinfunction "PD8_55") (pintype "bidirectional"))
    )
    (net (code "58") (name "/PD9") (class "Default")
      (node (ref "J4") (pin "10") (pinfunction "10_10") (pintype "passive"))
      (node (ref "R21") (pin "1") (pinfunction "1_1") (pintype "passive"))
      (node (ref "R22") (pin "1") (pinfunction "1_1") (pintype "passive"))
      (node (ref "R23") (pin "1") (pinfunction "1_1") (pintype "passive"))
      (node (ref "R24") (pin "1") (pinfunction "1_1") (pintype "passive"))
      (node (ref "R25") (pin "1") (pinfunction "1_1") (pintype "passive"))
      (node (ref "R26") (pin "1") (pinfunction "1_1") (pintype "passive"))
      (node (ref "U3") (pin "56") (pinfunction "PD9_56") (pintype "bidirectional"))
    )
    (net (code "59") (name "/PD10") (class "Default")
      (node (ref "U1_RIGHT") (pin "16") (pinfunction "~{EN}_16") (pintype "passive"))
      (node (ref "U2_LEFT") (pin "16") (pinfunction "~{EN}_16") (pintype "passive"))
      (node (ref "U3") (pin "57") (pinfunction "PD10_57") (pintype "bidirectional"))
    )
    (net (code "60") (name "/PD11") (class "Default")
      (node (ref "U2_LEFT") (pin "10") (pinfunction "STEP_10") (pintype "passive"))
      (node (ref "U3") (pin "58") (pinfunction "PD11_58") (pintype "bidirectional"))
    )
    (net (code "61") (name "/PD12") (class "Default")
      (node (ref "U2_LEFT") (pin "9") (pinfunction "DIR_9") (pintype "passive"))
      (node (ref "U3") (pin "59") (pinfunction "PD12_59") (pintype "bidirectional"))
    )
    (net (code "62") (name "/PD13") (class "Default")
      (node (ref "U1_RIGHT") (pin "10") (pinfunction "STEP_10") (pintype "passive"))
      (node (ref "U3") (pin "60") (pinfunction "PD13_60") (pintype "bidirectional"))
    )
    (net (code "63") (name "/PD14") (class "Default")
      (node (ref "U1_RIGHT") (pin "9") (pinfunction "DIR_9") (pintype "passive"))
      (node (ref "U3") (pin "61") (pinfunction "PD14_61") (pintype "bidirectional"))
    )
    (net (code "64") (name "/PD15") (class "Default")
      (node (ref "U3") (pin "62") (pinfunction "PD15_62") (pintype "bidirectional+no_connect"))
    )
    (net (code "65") (name "/PE0") (class "Default")
      (node (ref "J1_LEFT") (pin "4") (pinfunction "4_4") (pintype "passive"))
      (node (ref "U3") (pin "97") (pinfunction "PE0_97") (pintype "bidirectional"))
    )
    (net (code "66") (name "/PE1") (class "Default")
      (node (ref "J2_CENTRE") (pin "4") (pinfunction "4_4") (pintype "passive"))
      (node (ref "U3") (pin "98") (pinfunction "PE1_98") (pintype "bidirectional"))
    )
    (net (code "67") (name "/PE2") (class "Default")
      (node (ref "J5") (pin "44") (pinfunction "44_44") (pintype "passive"))
      (node (ref "U3") (pin "1") (pinfunction "PE2_1") (pintype "bidirectional"))
    )
    (net (code "68") (name "/PE3") (class "Default")
      (node (ref "J5") (pin "43") (pinfunction "43_43") (pintype "passive"))
      (node (ref "U3") (pin "2") (pinfunction "PE3_2") (pintype "bidirectional"))
      (node (ref "U4_LEFT") (pin "1") (pinfunction "~{ENABLE}_1") (pintype "input"))
      (node (ref "U5_RIGHT") (pin "1") (pinfunction "~{ENABLE}_1") (pintype "input"))
    )
    (net (code "69") (name "/PE4") (class "Default")
      (node (ref "U3") (pin "3") (pinfunction "PE4_3") (pintype "bidirectional"))
      (node (ref "U4_LEFT") (pin "7") (pinfunction "STEP_7") (pintype "input"))
    )
    (net (code "70") (name "/PE5") (class "Default")
      (node (ref "U3") (pin "4") (pinfunction "PE5_4") (pintype "bidirectional"))
      (node (ref "U4_LEFT") (pin "8") (pinfunction "DIR_8") (pintype "input"))
    )
    (net (code "71") (name "/PE6") (class "Default")
      (node (ref "U3") (pin "5") (pinfunction "PE6_5") (pintype "bidirectional"))
      (node (ref "U5_RIGHT") (pin "7") (pinfunction "STEP_7") (pintype "input"))
    )
    (net (code "72") (name "/PE7") (class "Default")
      (node (ref "U3") (pin "38") (pinfunction "PE7_38") (pintype "bidirectional"))
      (node (ref "U5_RIGHT") (pin "8") (pinfunction "DIR_8") (pintype "input"))
    )
    (net (code "73") (name "/PE8") (class "Default")
      (node (ref "J5") (pin "21") (pinfunction "21_21") (pintype "passive"))
      (node (ref "U3") (pin "39") (pinfunction "PE8_39") (pintype "bidirectional"))
    )
    (net (code "74") (name "/PE9") (class "Default")
      (node (ref "J5") (pin "20") (pinfunction "20_20") (pintype "passive"))
      (node (ref "U3") (pin "40") (pinfunction "PE9_40") (pintype "bidirectional"))
    )
    (net (code "75") (name "/PE10") (class "Default")
      (node (ref "J5") (pin "19") (pinfunction "19_19") (pintype "passive"))
      (node (ref "U3") (pin "41") (pinfunction "PE10_41") (pintype "bidirectional"))
    )
    (net (code "76") (name "/PE11") (class "Default")
      (node (ref "J5") (pin "18") (pinfunction "18_18") (pintype "passive"))
      (node (ref "U3") (pin "42") (pinfunction "PE11_42") (pintype "bidirectional"))
    )
    (net (code "77") (name "/PE12") (class "Default")
      (node (ref "J5") (pin "17") (pinfunction "17_17") (pintype "passive"))
      (node (ref "U3") (pin "43") (pinfunction "PE12_43") (pintype "bidirectional"))
    )
    (net (code "78") (name "/PE13") (class "Default")
      (node (ref "J5") (pin "16") (pinfunction "16_16") (pintype "passive"))
      (node (ref "U3") (pin "44") (pinfunction "PE13_44") (pintype "bidirectional"))
    )
    (net (code "79") (name "/PE14") (class "Default")
      (node (ref "J5") (pin "15") (pinfunction "15_15") (pintype "passive"))
      (node (ref "U3") (pin "45") (pinfunction "PE14_45") (pintype "bidirectional"))
    )
    (net (code "80") (name "/PE15") (class "Default")
      (node (ref "J5") (pin "14") (pinfunction "14_14") (pintype "passive"))
      (node (ref "U3") (pin "46") (pinfunction "PE15_46") (pintype "bidirectional"))
    )
    (net (code "81") (name "/RST") (class "Default")
      (node (ref "C3") (pin "2") (pinfunction "2_2") (pintype "passive"))
      (node (ref "R1") (pin "2") (pinfunction "2_2") (pintype "passive"))
      (node (ref "SW1") (pin "1") (pinfunction "1_1") (pintype "passive"))
      (node (ref "U3") (pin "14") (pinfunction "NRST_14") (pintype "bidirectional"))
    )
    (net (code "82") (name "/VBAT") (class "Default")
      (node (ref "C21") (pin "2") (pinfunction "2_2") (pintype "passive"))
      (node (ref "D1") (pin "3") (pinfunction "COMMON_CATHODE_3") (pintype "passive"))
      (node (ref "U3") (pin "6") (pinfunction "VBAT_6") (pintype "passive"))
    )
    (net (code "83") (name "/VDD") (class "Default")
      (node (ref "R29") (pin "2") (pinfunction "2_2") (pintype "passive"))
      (node (ref "R3") (pin "1") (pinfunction "1_1") (pintype "passive"))
    )
    (net (code "84") (name "/VDDA") (class "Default")
      (node (ref "C7") (pin "2") (pinfunction "2_2") (pintype "passive"))
      (node (ref "J5") (pin "7") (pinfunction "7_7") (pintype "passive"))
      (node (ref "R3") (pin "2") (pinfunction "2_2") (pintype "passive"))
      (node (ref "R4") (pin "2") (pinfunction "2_2") (pintype "passive"))
      (node (ref "U3") (pin "22") (pinfunction "VDDA_22") (pintype "bidirectional"))
    )
    (net (code "85") (name "/VREF+") (class "Default")
      (node (ref "J5") (pin "8") (pinfunction "8_8") (pintype "passive"))
      (node (ref "R4") (pin "1") (pinfunction "1_1") (pintype "passive"))
      (node (ref "U3") (pin "21") (pinfunction "VREF+_21") (pintype "bidirectional"))
    )
    (net (code "86") (name "3V3") (class "Default")
      (node (ref "C1") (pin "2") (pinfunction "2_2") (pintype "passive"))
      (node (ref "C10") (pin "2") (pinfunction "2_2") (pintype "passive"))
      (node (ref "C11") (pin "2") (pinfunction "2_2") (pintype "passive"))
      (node (ref "C12") (pin "2") (pinfunction "2_2") (pintype "passive"))
      (node (ref "C13") (pin "2") (pinfunction "2_2") (pintype "passive"))
      (node (ref "C14") (pin "2") (pinfunction "2_2") (pintype "passive"))
      (node (ref "C22") (pin "1") (pinfunction "1_1") (pintype "passive"))
      (node (ref "C6") (pin "2") (pinfunction "2_2") (pintype "passive"))
      (node (ref "C9") (pin "2") (pinfunction "2_2") (pintype "passive"))
      (node (ref "D1") (pin "1") (pinfunction "1_ANODE_1") (pintype "passive"))
      (node (ref "J1") (pin "2") (pinfunction "2_2") (pintype "passive"))
      (node (ref "J2") (pin "1") (pinfunction "1_1") (pintype "passive"))
      (node (ref "J4") (pin "3") (pinfunction "3_3") (pintype "passive"))
      (node (ref "J4") (pin "4") (pinfunction "4_4") (pintype "passive"))
      (node (ref "J5") (pin "1") (pinfunction "1_1") (pintype "passive"))
      (node (ref "J5") (pin "2") (pinfunction "2_2") (pintype "passive"))
      (node (ref "R1") (pin "1") (pinfunction "1_1") (pintype "passive"))
      (node (ref "R10") (pin "1") (pinfunction "1_1") (pintype "passive"))
      (node (ref "R11") (pin "1") (pinfunction "1_1") (pintype "passive"))
      (node (ref "R29") (pin "1") (pinfunction "1_1") (pintype "passive"))
      (node (ref "S1") (pin "A1") (pinfunction "A1_A1") (pintype "passive"))
      (node (ref "S1") (pin "A2") (pinfunction "A2_A2") (pintype "passive"))
      (node (ref "S2") (pin "A1") (pinfunction "A1_A1") (pintype "passive"))
      (node (ref "S2") (pin "A2") (pinfunction "A2_A2") (pintype "passive"))
      (node (ref "S3") (pin "A1") (pinfunction "A1_A1") (pintype "passive"))
      (node (ref "S4") (pin "A1") (pinfunction "A1_A1") (pintype "passive"))
      (node (ref "S5") (pin "A1") (pinfunction "A1_A1") (pintype "passive"))
      (node (ref "S6") (pin "A1") (pinfunction "A1_A1") (pintype "passive"))
      (node (ref "S7") (pin "A1") (pinfunction "A1_A1") (pintype "passive"))
      (node (ref "S7") (pin "A2") (pinfunction "A2_A2") (pintype "passive"))
      (node (ref "S7") (pin "A3") (pinfunction "A3_A3") (pintype "passive"))
      (node (ref "S8") (pin "A1") (pinfunction "A1_A1") (pintype "passive"))
      (node (ref "S8") (pin "A2") (pinfunction "A2_A2") (pintype "passive"))
      (node (ref "S8") (pin "A3") (pinfunction "A3_A3") (pintype "passive"))
      (node (ref "U1") (pin "3") (pinfunction "~{WP(IO2)}_3") (pintype "passive"))
      (node (ref "U1") (pin "7") (pinfunction "~{HOLD}/~{RESET(IO3)}_7") (pintype "passive"))
      (node (ref "U1") (pin "8") (pinfunction "VCC_8") (pintype "passive"))
      (node (ref "U1_RIGHT") (pin "2") (pinfunction "VIO_2") (pintype "passive"))
      (node (ref "U2") (pin "11") (pinfunction "BI2_11") (pintype "input"))
      (node (ref "U2") (pin "13") (pinfunction "STBY_13") (pintype "input"))
      (node (ref "U2") (pin "14") (pinfunction "AI1_14") (pintype "input"))
      (node (ref "U2") (pin "2") (pinfunction "VCC_2") (pintype "power_in"))
      (node (ref "U2_LEFT") (pin "2") (pinfunction "VIO_2") (pintype "passive"))
      (node (ref "U3") (pin "100") (pinfunction "VDD@6_100") (pintype "passive"))
      (node (ref "U3") (pin "11") (pinfunction "VDD@1_11") (pintype "passive"))
      (node (ref "U3") (pin "19") (pinfunction "VDD@2_19") (pintype "passive"))
      (node (ref "U3") (pin "28") (pinfunction "VDD@3_28") (pintype "passive"))
      (node (ref "U3") (pin "50") (pinfunction "VDD@4_50") (pintype "passive"))
      (node (ref "U3") (pin "75") (pinfunction "VDD@5_75") (pintype "bidirectional"))
      (node (ref "U4") (pin "11") (pinfunction "BI2_11") (pintype "input"))
      (node (ref "U4") (pin "13") (pinfunction "STBY_13") (pintype "input"))
      (node (ref "U4") (pin "14") (pinfunction "AI1_14") (pintype "input"))
      (node (ref "U4") (pin "2") (pinfunction "VCC_2") (pintype "power_in"))
    )
    (net (code "87") (name "GND") (class "Default")
      (node (ref "BT1") (pin "2") (pinfunction "-_2") (pintype "passive"))
      (node (ref "C1") (pin "1") (pinfunction "1_1") (pintype "passive"))
      (node (ref "C10") (pin "1") (pinfunction "1_1") (pintype "passive"))
      (node (ref "C11") (pin "1") (pinfunction "1_1") (pintype "passive"))
      (node (ref "C12") (pin "1") (pinfunction "1_1") (pintype "passive"))
      (node (ref "C13") (pin "1") (pinfunction "1_1") (pintype "passive"))
      (node (ref "C14") (pin "1") (pinfunction "1_1") (pintype "passive"))
      (node (ref "C17") (pin "1") (pinfunction "1_1") (pintype "passive"))
      (node (ref "C18") (pin "2") (pinfunction "2_2") (pintype "passive"))
      (node (ref "C2") (pin "1") (pinfunction "1_1") (pintype "passive"))
      (node (ref "C21") (pin "1") (pinfunction "1_1") (pintype "passive"))
      (node (ref "C22") (pin "2") (pinfunction "2_2") (pintype "passive"))
      (node (ref "C3") (pin "1") (pinfunction "1_1") (pintype "passive"))
      (node (ref "C4") (pin "1") (pinfunction "1_1") (pintype "passive"))
      (node (ref "C5") (pin "1") (pinfunction "1_1") (pintype "passive"))
      (node (ref "C6") (pin "1") (pinfunction "1_1") (pintype "passive"))
      (node (ref "C7") (pin "1") (pinfunction "1_1") (pintype "passive"))
      (node (ref "C8") (pin "1") (pinfunction "1_1") (pintype "passive"))
      (node (ref "C9") (pin "1") (pinfunction "1_1") (pintype "passive"))
      (node (ref "J1") (pin "3") (pinfunction "3_3") (pintype "passive"))
      (node (ref "J2") (pin "2") (pinfunction "2_2") (pintype "passive"))
      (node (ref "J3") (pin "5") (pinfunction "GND_5") (pintype "power_in"))
      (node (ref "J4") (pin "5") (pinfunction "5_5") (pintype "passive"))
      (node (ref "J4") (pin "6") (pinfunction "6_6") (pintype "passive"))
      (node (ref "J5") (pin "3") (pinfunction "3_3") (pintype "passive"))
      (node (ref "J5") (pin "4") (pinfunction "4_4") (pintype "passive"))
      (node (ref "J5") (pin "5") (pinfunction "5_5") (pintype "passive"))
      (node (ref "J5") (pin "6") (pinfunction "6_6") (pintype "passive"))
      (node (ref "J6") (pin "2") (pinfunction "2_2") (pintype "passive"))
      (node (ref "Q1") (pin "3") (pinfunction "S_3") (pintype "passive"))
      (node (ref "Q2") (pin "3") (pinfunction "S_3") (pintype "passive"))
      (node (ref "R12") (pin "1") (pinfunction "1_1") (pintype "passive"))
      (node (ref "R13") (pin "1") (pinfunction "1_1") (pintype "passive"))
      (node (ref "R14") (pin "1") (pinfunction "1_1") (pintype "passive"))
      (node (ref "R15") (pin "1") (pinfunction "1_1") (pintype "passive"))
      (node (ref "R16") (pin "1") (pinfunction "1_1") (pintype "passive"))
      (node (ref "R17") (pin "1") (pinfunction "1_1") (pintype "passive"))
      (node (ref "R18") (pin "2") (pinfunction "2_2") (pintype "passive"))
      (node (ref "R2") (pin "1") (pinfunction "1_1") (pintype "passive"))
      (node (ref "R5") (pin "1") (pinfunction "1_1") (pintype "passive"))
      (node (ref "R6") (pin "1") (pinfunction "1_1") (pintype "passive"))
      (node (ref "R7") (pin "1") (pinfunction "1_1") (pintype "passive"))
      (node (ref "R8") (pin "1") (pinfunction "1_1") (pintype "passive"))
      (node (ref "R9") (pin "1") (pinfunction "1_1") (pintype "passive"))
      (node (ref "SW1") (pin "2") (pinfunction "2_2") (pintype "passive"))
      (node (ref "U1") (pin "4") (pinfunction "GND_4") (pintype "power_in"))
      (node (ref "U1_RIGHT") (pin "1") (pinfunction "GND_1") (pintype "passive"))
      (node (ref "U2") (pin "12") (pinfunction "BI1_12") (pintype "input"))
      (node (ref "U2") (pin "15") (pinfunction "AI2_15") (pintype "input"))
      (node (ref "U2") (pin "3") (pinfunction "GND_3") (pintype "power_in"))
      (node (ref "U2") (pin "8") (pinfunction "GND_8") (pintype "power_in"))
      (node (ref "U2") (pin "9") (pinfunction "GND_9") (pintype "power_in"))
      (node (ref "U2_LEFT") (pin "1") (pinfunction "GND_1") (pintype "passive"))
      (node (ref "U3") (pin "10") (pinfunction "VSS@1_10") (pintype "passive"))
      (node (ref "U3") (pin "20") (pinfunction "VSSA_20") (pintype "passive"))
      (node (ref "U3") (pin "27") (pinfunction "VSS@2_27") (pintype "passive"))
      (node (ref "U3") (pin "74") (pinfunction "VSS@3_74") (pintype "passive"))
      (node (ref "U3") (pin "99") (pinfunction "VSS@4_99") (pintype "passive"))
      (node (ref "U4") (pin "12") (pinfunction "BI1_12") (pintype "input"))
      (node (ref "U4") (pin "15") (pinfunction "AI2_15") (pintype "input"))
      (node (ref "U4") (pin "3") (pinfunction "GND_3") (pintype "power_in"))
      (node (ref "U4") (pin "8") (pinfunction "GND_8") (pintype "power_in"))
      (node (ref "U4") (pin "9") (pinfunction "GND_9") (pintype "power_in"))
      (node (ref "U4_LEFT") (pin "15") (pinfunction "GND_15") (pintype "passive"))
      (node (ref "U5_RIGHT") (pin "15") (pinfunction "GND_15") (pintype "passive"))
    )
    (net (code "88") (name "Net-(BT1-+)") (class "Default")
      (node (ref "BT1") (pin "1") (pinfunction "+_1") (pintype "passive"))
      (node (ref "D1") (pin "2") (pinfunction "2_ANODE_2") (pintype "passive"))
    )
    (net (code "89") (name "Net-(C15-C)") (class "Default")
      (node (ref "C15") (pin "1") (pinfunction "C_1") (pintype "passive"))
      (node (ref "U1_RIGHT") (pin "7") (pinfunction "GND_7") (pintype "passive"))
    )
    (net (code "90") (name "Net-(C16-C)") (class "Default")
      (node (ref "C16") (pin "1") (pinfunction "C_1") (pintype "passive"))
      (node (ref "U2_LEFT") (pin "7") (pinfunction "GND_7") (pintype "passive"))
    )
    (net (code "91") (name "Net-(C19-C)") (class "Default")
      (node (ref "C19") (pin "1") (pinfunction "C_1") (pintype "passive"))
      (node (ref "U5_RIGHT") (pin "9") (pinfunction "GND_9") (pintype "power_in"))
    )
    (net (code "92") (name "Net-(C20-C)") (class "Default")
      (node (ref "C20") (pin "1") (pinfunction "C_1") (pintype "passive"))
      (node (ref "U4_LEFT") (pin "9") (pinfunction "GND_9") (pintype "power_in"))
    )
    (net (code "93") (name "Net-(D2-A)") (class "Default")
      (node (ref "D2") (pin "2") (pinfunction "A_2") (pintype "passive"))
      (node (ref "J10") (pin "2") (pinfunction "2_2") (pintype "passive"))
      (node (ref "Q1") (pin "2") (pinfunction "D_2") (pintype "passive"))
    )
    (net (code "94") (name "Net-(D3-A)") (class "Default")
      (node (ref "D3") (pin "2") (pinfunction "A_2") (pintype "passive"))
      (node (ref "J12") (pin "2") (pinfunction "2_2") (pintype "passive"))
      (node (ref "Q2") (pin "2") (pinfunction "D_2") (pintype "passive"))
    )
    (net (code "95") (name "Net-(J3-D+)") (class "Default")
      (node (ref "J3") (pin "3") (pinfunction "D+_3") (pintype "bidirectional"))
      (node (ref "R19") (pin "1") (pinfunction "1_1") (pintype "passive"))
    )
    (net (code "96") (name "Net-(J3-D-)") (class "Default")
      (node (ref "J3") (pin "2") (pinfunction "D-_2") (pintype "bidirectional"))
      (node (ref "R20") (pin "1") (pinfunction "1_1") (pintype "passive"))
    )
    (net (code "97") (name "Net-(J3-SHIELD-PadSH1)") (class "Default")
      (node (ref "J3") (pin "SH1") (pinfunction "SHIELD_SH1") (pintype "passive"))
      (node (ref "J3") (pin "SH2") (pinfunction "SHIELD_SH2") (pintype "passive"))
      (node (ref "J3") (pin "SH3") (pinfunction "SHIELD_SH3") (pintype "passive"))
      (node (ref "J3") (pin "SH4") (pinfunction "SHIELD_SH4") (pintype "passive"))
      (node (ref "J3") (pin "SH5") (pinfunction "SHIELD_SH5") (pintype "passive"))
      (node (ref "J3") (pin "SH6") (pinfunction "SHIELD_SH6") (pintype "passive"))
      (node (ref "R18") (pin "1") (pinfunction "1_1") (pintype "passive"))
    )
    (net (code "98") (name "Net-(J3-VCC)") (class "Default")
      (node (ref "FB1") (pin "2") (pinfunction "2_2") (pintype "passive"))
      (node (ref "J3") (pin "1") (pinfunction "VCC_1") (pintype "power_in"))
    )
    (net (code "99") (name "Net-(Q1-G)") (class "Default")
      (node (ref "Q1") (pin "1") (pinfunction "G_1") (pintype "passive"))
      (node (ref "R27") (pin "2") (pinfunction "2_2") (pintype "passive"))
    )
    (net (code "100") (name "Net-(Q2-G)") (class "Default")
      (node (ref "Q2") (pin "1") (pinfunction "G_1") (pintype "passive"))
      (node (ref "R28") (pin "2") (pinfunction "2_2") (pintype "passive"))
    )
    (net (code "101") (name "Net-(U1_RIGHT-M1A)") (class "Default")
      (node (ref "P1") (pin "1") (pinfunction "1_1") (pintype "passive"))
      (node (ref "U1_RIGHT") (pin "4") (pinfunction "M1A_4") (pintype "passive"))
    )
    (net (code "102") (name "Net-(U1_RIGHT-M1B)") (class "Default")
      (node (ref "P1") (pin "3") (pinfunction "3_3") (pintype "passive"))
      (node (ref "U1_RIGHT") (pin "3") (pinfunction "M1B_3") (pintype "passive"))
    )
    (net (code "103") (name "Net-(U1_RIGHT-M2A)") (class "Default")
      (node (ref "P1") (pin "2") (pinfunction "2_2") (pintype "passive"))
      (node (ref "U1_RIGHT") (pin "5") (pinfunction "M2A_5") (pintype "passive"))
    )
    (net (code "104") (name "Net-(U1_RIGHT-M2B)") (class "Default")
      (node (ref "P1") (pin "4") (pinfunction "4_4") (pintype "passive"))
      (node (ref "U1_RIGHT") (pin "6") (pinfunction "M2B_6") (pintype "passive"))
    )
    (net (code "105") (name "Net-(U1_RIGHT-MS1)") (class "Default")
      (node (ref "R5") (pin "2") (pinfunction "2_2") (pintype "passive"))
      (node (ref "S1") (pin "2") (pinfunction "2_2") (pintype "passive"))
      (node (ref "U1_RIGHT") (pin "15") (pinfunction "MS1_15") (pintype "passive"))
    )
    (net (code "106") (name "Net-(U1_RIGHT-MS2)") (class "Default")
      (node (ref "R6") (pin "2") (pinfunction "2_2") (pintype "passive"))
      (node (ref "S1") (pin "1") (pinfunction "1_1") (pintype "passive"))
      (node (ref "U1_RIGHT") (pin "14") (pinfunction "MS2_14") (pintype "passive"))
    )
    (net (code "107") (name "Net-(U1_RIGHT-PDN)") (class "Default")
      (node (ref "R23") (pin "2") (pinfunction "2_2") (pintype "passive"))
      (node (ref "U1_RIGHT") (pin "11") (pinfunction "PDN_11") (pintype "passive"))
    )
    (net (code "108") (name "Net-(U1_RIGHT-UART)") (class "Default")
      (node (ref "R24") (pin "2") (pinfunction "2_2") (pintype "passive"))
      (node (ref "U1_RIGHT") (pin "12") (pinfunction "UART_12") (pintype "passive"))
    )
    (net (code "109") (name "Net-(U2-A01)") (class "Default")
      (node (ref "J7") (pin "1") (pinfunction "1_1") (pintype "passive"))
      (node (ref "U2") (pin "4") (pinfunction "A01_4") (pintype "output"))
    )
    (net (code "110") (name "Net-(U2-A02)") (class "Default")
      (node (ref "J7") (pin "2") (pinfunction "2_2") (pintype "passive"))
      (node (ref "U2") (pin "5") (pinfunction "A02_5") (pintype "output"))
    )
    (net (code "111") (name "Net-(U2-B01)") (class "Default")
      (node (ref "J8") (pin "1") (pinfunction "1_1") (pintype "passive"))
      (node (ref "U2") (pin "7") (pinfunction "B01_7") (pintype "output"))
    )
    (net (code "112") (name "Net-(U2-B02)") (class "Default")
      (node (ref "J8") (pin "2") (pinfunction "2_2") (pintype "passive"))
      (node (ref "U2") (pin "6") (pinfunction "B02_6") (pintype "output"))
    )
    (net (code "113") (name "Net-(U2-PWMA)") (class "Default")
      (node (ref "U2") (pin "10") (pinfunction "PWMB_10") (pintype "input"))
      (node (ref "U2") (pin "16") (pinfunction "PWMA_16") (pintype "input"))
      (node (ref "U3") (pin "35") (pinfunction "PB0_35") (pintype "passive"))
    )
    (net (code "114") (name "Net-(U2_LEFT-M1A)") (class "Default")
      (node (ref "P2") (pin "1") (pinfunction "1_1") (pintype "passive"))
      (node (ref "U2_LEFT") (pin "4") (pinfunction "M1A_4") (pintype "passive"))
    )
    (net (code "115") (name "Net-(U2_LEFT-M1B)") (class "Default")
      (node (ref "P2") (pin "3") (pinfunction "3_3") (pintype "passive"))
      (node (ref "U2_LEFT") (pin "3") (pinfunction "M1B_3") (pintype "passive"))
    )
    (net (code "116") (name "Net-(U2_LEFT-M2A)") (class "Default")
      (node (ref "P2") (pin "2") (pinfunction "2_2") (pintype "passive"))
      (node (ref "U2_LEFT") (pin "5") (pinfunction "M2A_5") (pintype "passive"))
    )
    (net (code "117") (name "Net-(U2_LEFT-M2B)") (class "Default")
      (node (ref "P2") (pin "4") (pinfunction "4_4") (pintype "passive"))
      (node (ref "U2_LEFT") (pin "6") (pinfunction "M2B_6") (pintype "passive"))
    )
    (net (code "118") (name "Net-(U2_LEFT-MS1)") (class "Default")
      (node (ref "R7") (pin "2") (pinfunction "2_2") (pintype "passive"))
      (node (ref "S2") (pin "2") (pinfunction "2_2") (pintype "passive"))
      (node (ref "U2_LEFT") (pin "15") (pinfunction "MS1_15") (pintype "passive"))
    )
    (net (code "119") (name "Net-(U2_LEFT-MS2)") (class "Default")
      (node (ref "R8") (pin "2") (pinfunction "2_2") (pintype "passive"))
      (node (ref "S2") (pin "1") (pinfunction "1_1") (pintype "passive"))
      (node (ref "U2_LEFT") (pin "14") (pinfunction "MS2_14") (pintype "passive"))
    )
    (net (code "120") (name "Net-(U2_LEFT-PDN)") (class "Default")
      (node (ref "R21") (pin "2") (pinfunction "2_2") (pintype "passive"))
      (node (ref "U2_LEFT") (pin "11") (pinfunction "PDN_11") (pintype "passive"))
    )
    (net (code "121") (name "Net-(U2_LEFT-UART)") (class "Default")
      (node (ref "R22") (pin "2") (pinfunction "2_2") (pintype "passive"))
      (node (ref "U2_LEFT") (pin "12") (pinfunction "UART_12") (pintype "passive"))
    )
    (net (code "122") (name "Net-(U3-PH0)") (class "Default")
      (node (ref "C5") (pin "2") (pinfunction "2_2") (pintype "passive"))
      (node (ref "U3") (pin "12") (pinfunction "PH0_12") (pintype "bidirectional"))
      (node (ref "Y1") (pin "2") (pinfunction "2_2") (pintype "passive"))
    )
    (net (code "123") (name "Net-(U3-PH1)") (class "Default")
      (node (ref "C4") (pin "2") (pinfunction "2_2") (pintype "passive"))
      (node (ref "U3") (pin "13") (pinfunction "PH1_13") (pintype "bidirectional"))
      (node (ref "Y1") (pin "1") (pinfunction "1_1") (pintype "passive"))
    )
    (net (code "124") (name "Net-(U3-VCAP_1)") (class "Default")
      (node (ref "C8") (pin "2") (pinfunction "2_2") (pintype "passive"))
      (node (ref "U3") (pin "49") (pinfunction "VCAP_1_49") (pintype "bidirectional"))
    )
    (net (code "125") (name "Net-(U3-VCAP_2)") (class "Default")
      (node (ref "C2") (pin "2") (pinfunction "2_2") (pintype "passive"))
      (node (ref "U3") (pin "73") (pinfunction "VCAP_2_73") (pintype "bidirectional"))
    )
    (net (code "126") (name "Net-(U4-A01)") (class "Default")
      (node (ref "J9") (pin "1") (pinfunction "1_1") (pintype "passive"))
      (node (ref "U4") (pin "4") (pinfunction "A01_4") (pintype "output"))
    )
    (net (code "127") (name "Net-(U4-A02)") (class "Default")
      (node (ref "J9") (pin "2") (pinfunction "2_2") (pintype "passive"))
      (node (ref "U4") (pin "5") (pinfunction "A02_5") (pintype "output"))
    )
    (net (code "128") (name "Net-(U4-B01)") (class "Default")
      (node (ref "J11") (pin "1") (pinfunction "1_1") (pintype "passive"))
      (node (ref "U4") (pin "7") (pinfunction "B01_7") (pintype "output"))
    )
    (net (code "129") (name "Net-(U4-B02)") (class "Default")
      (node (ref "J11") (pin "2") (pinfunction "2_2") (pintype "passive"))
      (node (ref "U4") (pin "6") (pinfunction "B02_6") (pintype "output"))
    )
    (net (code "130") (name "Net-(U4_LEFT-1A)") (class "Default")
      (node (ref "P4") (pin "1") (pinfunction "1_1") (pintype "passive"))
      (node (ref "U4_LEFT") (pin "12") (pinfunction "1A_12") (pintype "output"))
    )
    (net (code "131") (name "Net-(U4_LEFT-1B)") (class "Default")
      (node (ref "P4") (pin "2") (pinfunction "2_2") (pintype "passive"))
      (node (ref "U4_LEFT") (pin "11") (pinfunction "1B_11") (pintype "output"))
    )
    (net (code "132") (name "Net-(U4_LEFT-2A)") (class "Default")
      (node (ref "P4") (pin "3") (pinfunction "3_3") (pintype "passive"))
      (node (ref "U4_LEFT") (pin "13") (pinfunction "2A_13") (pintype "output"))
    )
    (net (code "133") (name "Net-(U4_LEFT-2B)") (class "Default")
      (node (ref "P4") (pin "4") (pinfunction "4_4") (pintype "passive"))
      (node (ref "U4_LEFT") (pin "14") (pinfunction "2B_14") (pintype "output"))
    )
    (net (code "134") (name "Net-(U4_LEFT-MS1)") (class "Default")
      (node (ref "R17") (pin "2") (pinfunction "2_2") (pintype "passive"))
      (node (ref "S8") (pin "3") (pinfunction "3_3") (pintype "passive"))
      (node (ref "U4_LEFT") (pin "2") (pinfunction "MS1_2") (pintype "input"))
    )
    (net (code "135") (name "Net-(U4_LEFT-MS2)") (class "Default")
      (node (ref "R16") (pin "2") (pinfunction "2_2") (pintype "passive"))
      (node (ref "S8") (pin "2") (pinfunction "2_2") (pintype "passive"))
      (node (ref "U4_LEFT") (pin "3") (pinfunction "MS2_3") (pintype "input"))
    )
    (net (code "136") (name "Net-(U4_LEFT-MS3)") (class "Default")
      (node (ref "R13") (pin "2") (pinfunction "2_2") (pintype "passive"))
      (node (ref "S8") (pin "1") (pinfunction "1_1") (pintype "passive"))
      (node (ref "U4_LEFT") (pin "4") (pinfunction "MS3_4") (pintype "input"))
    )
    (net (code "137") (name "Net-(U4_LEFT-VDD)") (class "Default")
      (node (ref "S3") (pin "1") (pinfunction "1_1") (pintype "passive"))
      (node (ref "U4_LEFT") (pin "10") (pinfunction "VDD_10") (pintype "power_in"))
    )
    (net (code "138") (name "Net-(U4_LEFT-~{RESET})") (class "Default")
      (node (ref "S6") (pin "1") (pinfunction "1_1") (pintype "passive"))
      (node (ref "U4_LEFT") (pin "5") (pinfunction "~{RESET}_5") (pintype "input"))
      (node (ref "U4_LEFT") (pin "6") (pinfunction "~{SLEEP}_6") (pintype "input"))
    )
    (net (code "139") (name "Net-(U5_RIGHT-1A)") (class "Default")
      (node (ref "P3") (pin "1") (pinfunction "1_1") (pintype "passive"))
      (node (ref "U5_RIGHT") (pin "12") (pinfunction "1A_12") (pintype "output"))
    )
    (net (code "140") (name "Net-(U5_RIGHT-1B)") (class "Default")
      (node (ref "P3") (pin "2") (pinfunction "2_2") (pintype "passive"))
      (node (ref "U5_RIGHT") (pin "11") (pinfunction "1B_11") (pintype "output"))
    )
    (net (code "141") (name "Net-(U5_RIGHT-2A)") (class "Default")
      (node (ref "P3") (pin "3") (pinfunction "3_3") (pintype "passive"))
      (node (ref "U5_RIGHT") (pin "13") (pinfunction "2A_13") (pintype "output"))
    )
    (net (code "142") (name "Net-(U5_RIGHT-2B)") (class "Default")
      (node (ref "P3") (pin "4") (pinfunction "4_4") (pintype "passive"))
      (node (ref "U5_RIGHT") (pin "14") (pinfunction "2B_14") (pintype "output"))
    )
    (net (code "143") (name "Net-(U5_RIGHT-MS1)") (class "Default")
      (node (ref "R15") (pin "2") (pinfunction "2_2") (pintype "passive"))
      (node (ref "S7") (pin "3") (pinfunction "3_3") (pintype "passive"))
      (node (ref "U5_RIGHT") (pin "2") (pinfunction "MS1_2") (pintype "input"))
    )
    (net (code "144") (name "Net-(U5_RIGHT-MS2)") (class "Default")
      (node (ref "R14") (pin "2") (pinfunction "2_2") (pintype "passive"))
      (node (ref "S7") (pin "2") (pinfunction "2_2") (pintype "passive"))
      (node (ref "U5_RIGHT") (pin "3") (pinfunction "MS2_3") (pintype "input"))
    )
    (net (code "145") (name "Net-(U5_RIGHT-MS3)") (class "Default")
      (node (ref "R12") (pin "2") (pinfunction "2_2") (pintype "passive"))
      (node (ref "S7") (pin "1") (pinfunction "1_1") (pintype "passive"))
      (node (ref "U5_RIGHT") (pin "4") (pinfunction "MS3_4") (pintype "input"))
    )
    (net (code "146") (name "Net-(U5_RIGHT-VDD)") (class "Default")
      (node (ref "S4") (pin "1") (pinfunction "1_1") (pintype "passive"))
      (node (ref "U5_RIGHT") (pin "10") (pinfunction "VDD_10") (pintype "power_in"))
    )
    (net (code "147") (name "Net-(U5_RIGHT-~{RESET})") (class "Default")
      (node (ref "S5") (pin "1") (pinfunction "1_1") (pintype "passive"))
      (node (ref "U5_RIGHT") (pin "5") (pinfunction "~{RESET}_5") (pintype "input"))
      (node (ref "U5_RIGHT") (pin "6") (pinfunction "~{SLEEP}_6") (pintype "input"))
    )
    (net (code "148") (name "unconnected-(J3-ID-Pad4)") (class "Default")
      (node (ref "J3") (pin "4") (pinfunction "ID_4") (pintype "bidirectional+no_connect"))
    )
    (net (code "149") (name "unconnected-(J4-Pad8)") (class "Default")
      (node (ref "J4") (pin "8") (pinfunction "8_8") (pintype "passive+no_connect"))
    )
    (net (code "150") (name "unconnected-(J4-Pad9)") (class "Default")
      (node (ref "J4") (pin "9") (pinfunction "9_9") (pintype "passive+no_connect"))
    )
    (net (code "151") (name "unconnected-(J4-Pad11)") (class "Default")
      (node (ref "J4") (pin "11") (pinfunction "11_11") (pintype "passive+no_connect"))
    )
    (net (code "152") (name "unconnected-(J4-Pad12)") (class "Default")
      (node (ref "J4") (pin "12") (pinfunction "12_12") (pintype "passive+no_connect"))
    )
    (net (code "153") (name "unconnected-(J4-Pad13)") (class "Default")
      (node (ref "J4") (pin "13") (pinfunction "13_13") (pintype "passive+no_connect"))
    )
    (net (code "154") (name "unconnected-(J4-Pad14)") (class "Default")
      (node (ref "J4") (pin "14") (pinfunction "14_14") (pintype "passive+no_connect"))
    )
    (net (code "155") (name "unconnected-(J4-Pad15)") (class "Default")
      (node (ref "J4") (pin "15") (pinfunction "15_15") (pintype "passive+no_connect"))
    )
    (net (code "156") (name "unconnected-(J4-Pad16)") (class "Default")
      (node (ref "J4") (pin "16") (pinfunction "16_16") (pintype "passive+no_connect"))
    )
    (net (code "157") (name "unconnected-(J4-Pad17)") (class "Default")
      (node (ref "J4") (pin "17") (pinfunction "17_17") (pintype "passive+no_connect"))
    )
    (net (code "158") (name "unconnected-(J4-Pad18)") (class "Default")
      (node (ref "J4") (pin "18") (pinfunction "18_18") (pintype "passive+no_connect"))
    )
    (net (code "159") (name "unconnected-(J4-Pad19)") (class "Default")
      (node (ref "J4") (pin "19") (pinfunction "19_19") (pintype "passive+no_connect"))
    )
    (net (code "160") (name "unconnected-(J4-Pad20)") (class "Default")
      (node (ref "J4") (pin "20") (pinfunction "20_20") (pintype "passive+no_connect"))
    )
    (net (code "161") (name "unconnected-(J4-Pad33)") (class "Default")
      (node (ref "J4") (pin "33") (pinfunction "33_33") (pintype "passive"))
    )
    (net (code "162") (name "unconnected-(J4-Pad36)") (class "Default")
      (node (ref "J4") (pin "36") (pinfunction "36_36") (pintype "passive+no_connect"))
    )
    (net (code "163") (name "unconnected-(J4-Pad39)") (class "Default")
      (node (ref "J4") (pin "39") (pinfunction "39_39") (pintype "passive+no_connect"))
    )
    (net (code "164") (name "unconnected-(J4-Pad40)") (class "Default")
      (node (ref "J4") (pin "40") (pinfunction "40_40") (pintype "passive+no_connect"))
    )
    (net (code "165") (name "unconnected-(J4-Pad41)") (class "Default")
      (node (ref "J4") (pin "41") (pinfunction "41_41") (pintype "passive+no_connect"))
    )
    (net (code "166") (name "unconnected-(J4-Pad42)") (class "Default")
      (node (ref "J4") (pin "42") (pinfunction "42_42") (pintype "passive+no_connect"))
    )
    (net (code "167") (name "unconnected-(J4-Pad43)") (class "Default")
      (node (ref "J4") (pin "43") (pinfunction "43_43") (pintype "passive+no_connect"))
    )
    (net (code "168") (name "unconnected-(J4-Pad44)") (class "Default")
      (node (ref "J4") (pin "44") (pinfunction "44_44") (pintype "passive+no_connect"))
    )
    (net (code "169") (name "unconnected-(J5-Pad22)") (class "Default")
      (node (ref "J5") (pin "22") (pinfunction "22_22") (pintype "passive+no_connect"))
    )
    (net (code "170") (name "unconnected-(J5-Pad24)") (class "Default")
      (node (ref "J5") (pin "24") (pinfunction "24_24") (pintype "passive+no_connect"))
    )
    (net (code "171") (name "unconnected-(J5-Pad25)") (class "Default")
      (node (ref "J5") (pin "25") (pinfunction "25_25") (pintype "passive+no_connect"))
    )
    (net (code "172") (name "unconnected-(J5-Pad26)") (class "Default")
      (node (ref "J5") (pin "26") (pinfunction "26_26") (pintype "passive+no_connect"))
    )
    (net (code "173") (name "unconnected-(J5-Pad27)") (class "Default")
      (node (ref "J5") (pin "27") (pinfunction "27_27") (pintype "passive+no_connect"))
    )
    (net (code "174") (name "unconnected-(J5-Pad28)") (class "Default")
      (node (ref "J5") (pin "28") (pinfunction "28_28") (pintype "passive+no_connect"))
    )
    (net (code "175") (name "unconnected-(J5-Pad29)") (class "Default")
      (node (ref "J5") (pin "29") (pinfunction "29_29") (pintype "passive+no_connect"))
    )
    (net (code "176") (name "unconnected-(J5-Pad30)") (class "Default")
      (node (ref "J5") (pin "30") (pinfunction "30_30") (pintype "passive+no_connect"))
    )
    (net (code "177") (name "unconnected-(J5-Pad33)") (class "Default")
      (node (ref "J5") (pin "33") (pinfunction "33_33") (pintype "passive+no_connect"))
    )
    (net (code "178") (name "unconnected-(J5-Pad35)") (class "Default")
      (node (ref "J5") (pin "35") (pinfunction "35_35") (pintype "passive+no_connect"))
    )
    (net (code "179") (name "unconnected-(J5-Pad37)") (class "Default")
      (node (ref "J5") (pin "37") (pinfunction "37_37") (pintype "passive+no_connect"))
    )
    (net (code "180") (name "unconnected-(J5-Pad38)") (class "Default")
      (node (ref "J5") (pin "38") (pinfunction "38_38") (pintype "passive+no_connect"))
    )
    (net (code "181") (name "unconnected-(J5-Pad39)") (class "Default")
      (node (ref "J5") (pin "39") (pinfunction "39_39") (pintype "passive+no_connect"))
    )
    (net (code "182") (name "unconnected-(J5-Pad40)") (class "Default")
      (node (ref "J5") (pin "40") (pinfunction "40_40") (pintype "passive+no_connect"))
    )
    (net (code "183") (name "unconnected-(J5-Pad41)") (class "Default")
      (node (ref "J5") (pin "41") (pinfunction "41_41") (pintype "passive+no_connect"))
    )
    (net (code "184") (name "unconnected-(J5-Pad42)") (class "Default")
      (node (ref "J5") (pin "42") (pinfunction "42_42") (pintype "passive+no_connect"))
    )
    (net (code "185") (name "unconnected-(MH1-Pad1)") (class "Default")
      (node (ref "MH1") (pin "1") (pinfunction "1_1") (pintype "passive+no_connect"))
    )
    (net (code "186") (name "unconnected-(MH2-Pad1)") (class "Default")
      (node (ref "MH2") (pin "1") (pinfunction "1_1") (pintype "passive+no_connect"))
    )
    (net (code "187") (name "unconnected-(MH3-Pad1)") (class "Default")
      (node (ref "MH3") (pin "1") (pinfunction "1_1") (pintype "passive+no_connect"))
    )
    (net (code "188") (name "unconnected-(MH4-Pad1)") (class "Default")
      (node (ref "MH4") (pin "1") (pinfunction "1_1") (pintype "passive+no_connect"))
    )
    (net (code "189") (name "unconnected-(S3-Pad2)") (class "Default")
      (node (ref "S3") (pin "2") (pinfunction "2_2") (pintype "passive+no_connect"))
    )
    (net (code "190") (name "unconnected-(S3-PadA2)") (class "Default")
      (node (ref "S3") (pin "A2") (pinfunction "A2_A2") (pintype "passive+no_connect"))
    )
    (net (code "191") (name "unconnected-(S4-Pad2)") (class "Default")
      (node (ref "S4") (pin "2") (pinfunction "2_2") (pintype "passive+no_connect"))
    )
    (net (code "192") (name "unconnected-(S4-PadA2)") (class "Default")
      (node (ref "S4") (pin "A2") (pinfunction "A2_A2") (pintype "passive+no_connect"))
    )
    (net (code "193") (name "unconnected-(S5-Pad2)") (class "Default")
      (node (ref "S5") (pin "2") (pinfunction "2_2") (pintype "passive+no_connect"))
    )
    (net (code "194") (name "unconnected-(S5-PadA2)") (class "Default")
      (node (ref "S5") (pin "A2") (pinfunction "A2_A2") (pintype "passive+no_connect"))
    )
    (net (code "195") (name "unconnected-(S6-Pad2)") (class "Default")
      (node (ref "S6") (pin "2") (pinfunction "2_2") (pintype "passive+no_connect"))
    )
    (net (code "196") (name "unconnected-(S6-PadA2)") (class "Default")
      (node (ref "S6") (pin "A2") (pinfunction "A2_A2") (pintype "passive+no_connect"))
    )
    (net (code "197") (name "unconnected-(U1_RIGHT-DIAG-Pad18)") (class "Default")
      (node (ref "U1_RIGHT") (pin "18") (pinfunction "DIAG_18") (pintype "passive+no_connect"))
    )
    (net (code "198") (name "unconnected-(U1_RIGHT-INDEX-Pad17)") (class "Default")
      (node (ref "U1_RIGHT") (pin "17") (pinfunction "INDEX_17") (pintype "passive+no_connect"))
    )
    (net (code "199") (name "unconnected-(U1_RIGHT-SPRD-Pad13)") (class "Default")
      (node (ref "U1_RIGHT") (pin "13") (pinfunction "SPRD_13") (pintype "passive+no_connect"))
    )
    (net (code "200") (name "unconnected-(U2_LEFT-DIAG-Pad18)") (class "Default")
      (node (ref "U2_LEFT") (pin "18") (pinfunction "DIAG_18") (pintype "passive+no_connect"))
    )
    (net (code "201") (name "unconnected-(U2_LEFT-INDEX-Pad17)") (class "Default")
      (node (ref "U2_LEFT") (pin "17") (pinfunction "INDEX_17") (pintype "passive+no_connect"))
    )
    (net (code "202") (name "unconnected-(U2_LEFT-SPRD-Pad13)") (class "Default")
      (node (ref "U2_LEFT") (pin "13") (pinfunction "SPRD_13") (pintype "passive+no_connect"))
    )
    (net (code "203") (name "unconnected-(U3-PA5-Pad30)") (class "Default")
      (node (ref "U3") (pin "30") (pinfunction "PA5_30") (pintype "passive+no_connect"))
    )
    (net (code "204") (name "unconnected-(U3-PB8-Pad95)") (class "Default")
      (node (ref "U3") (pin "95") (pinfunction "PB8_95") (pintype "bidirectional+no_connect"))
    )
  )
)
